# schematic.net
KiCad netlist of a schematic drawn in EAGLE
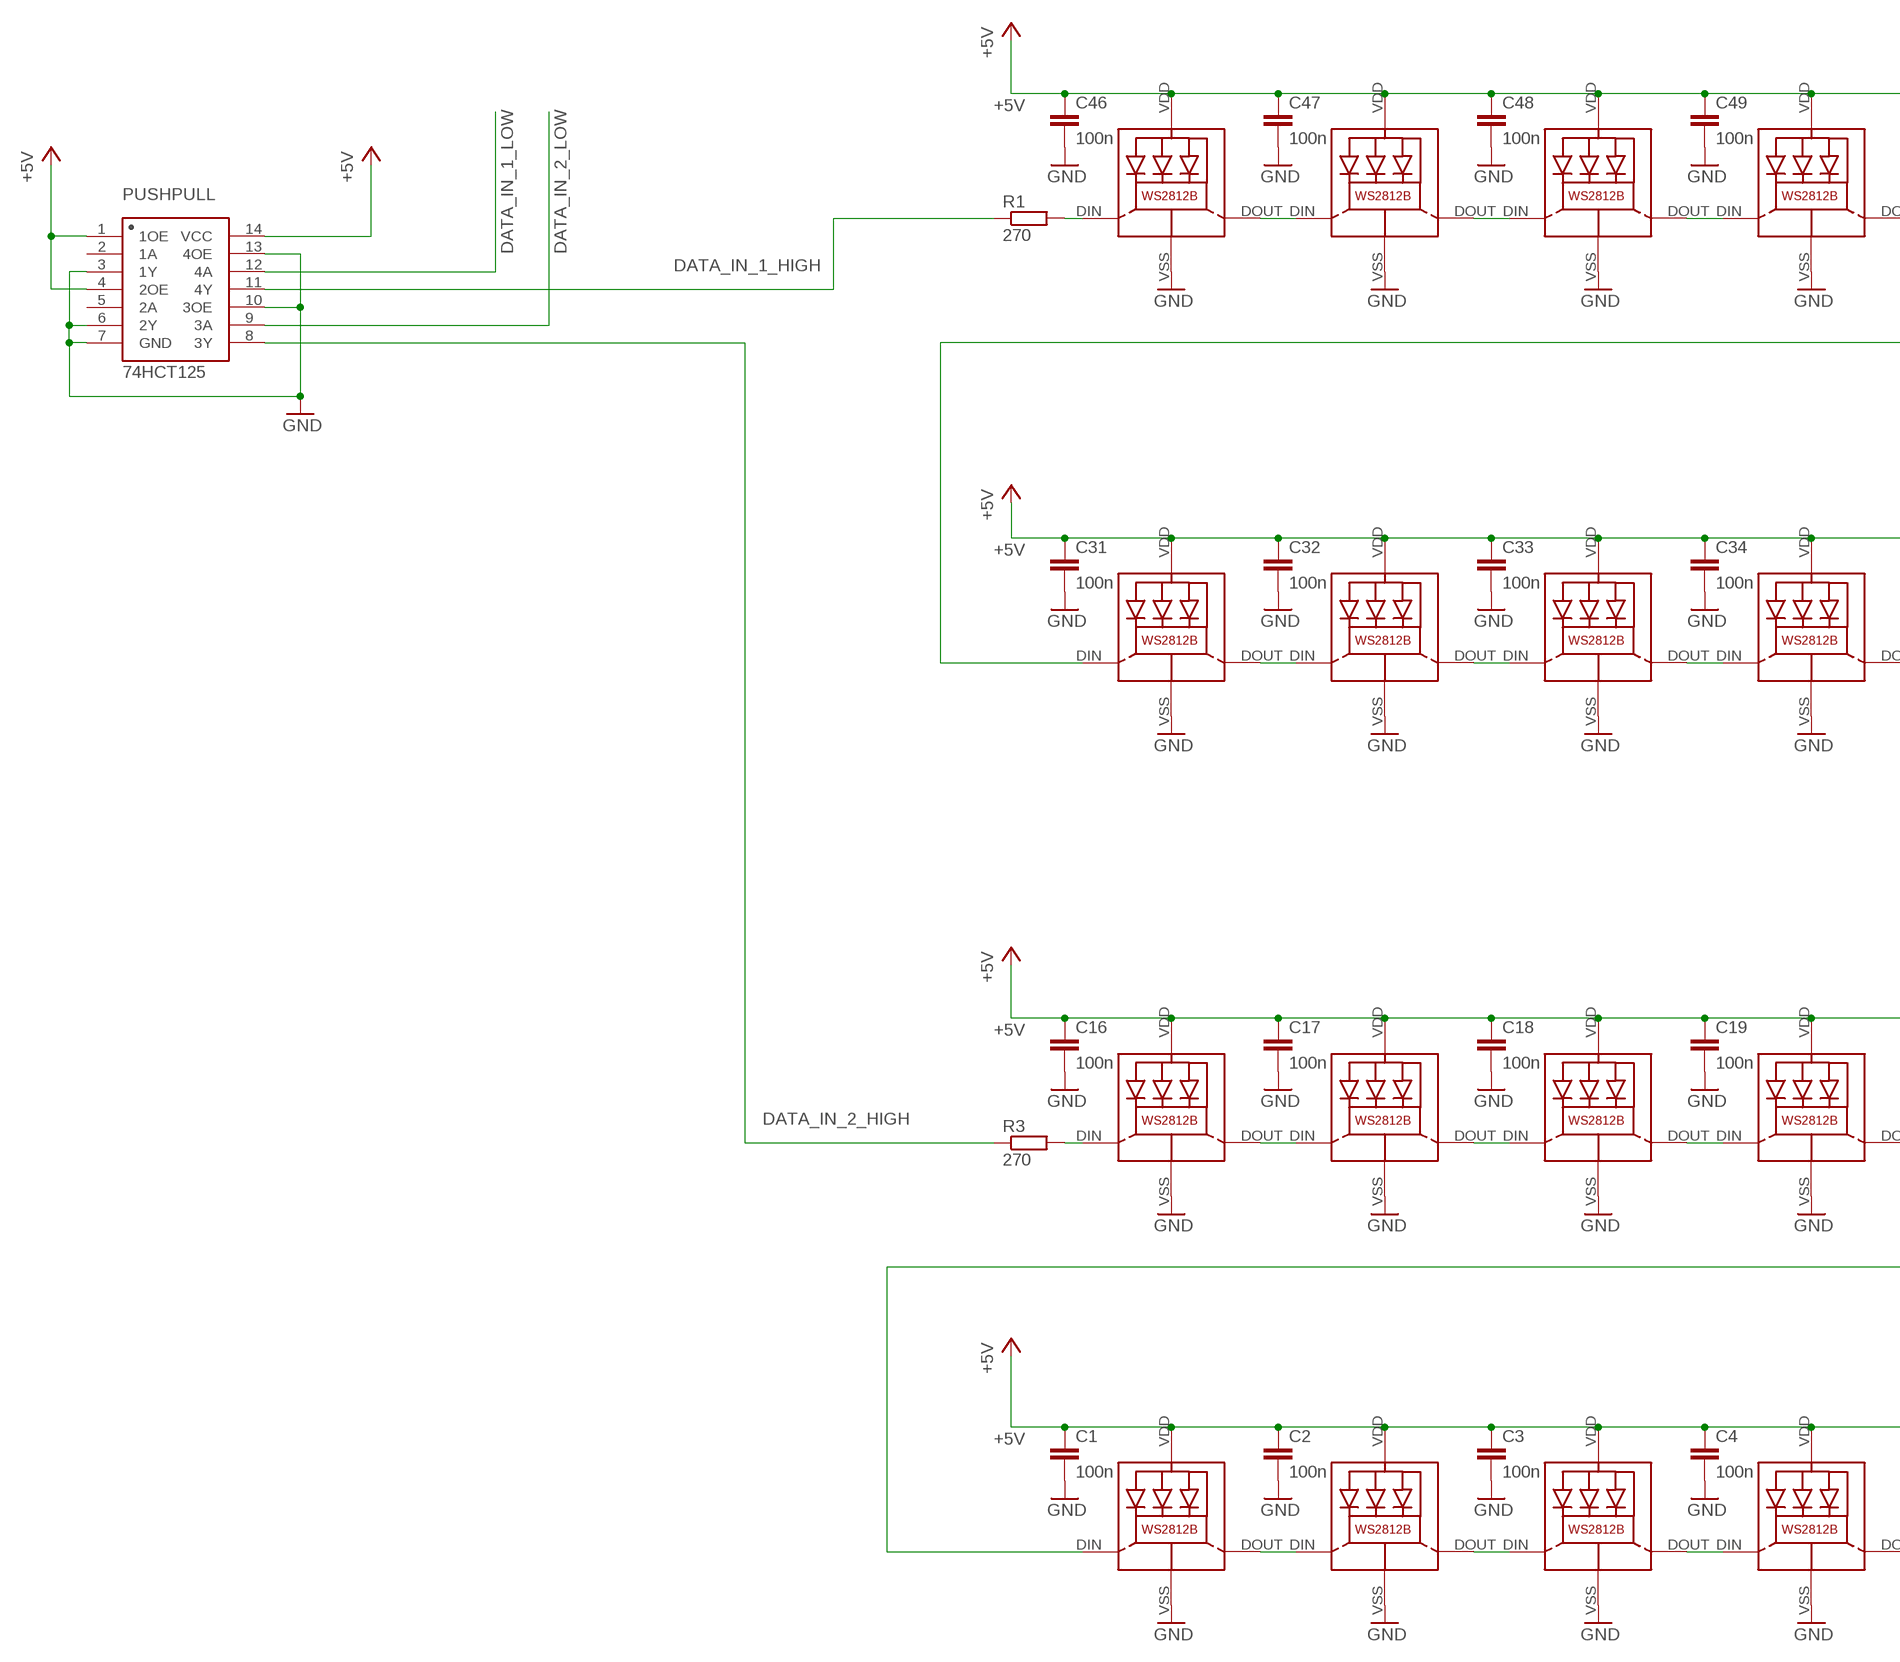
[diagram p0: schematic, sheet 1, part 1 of 2]
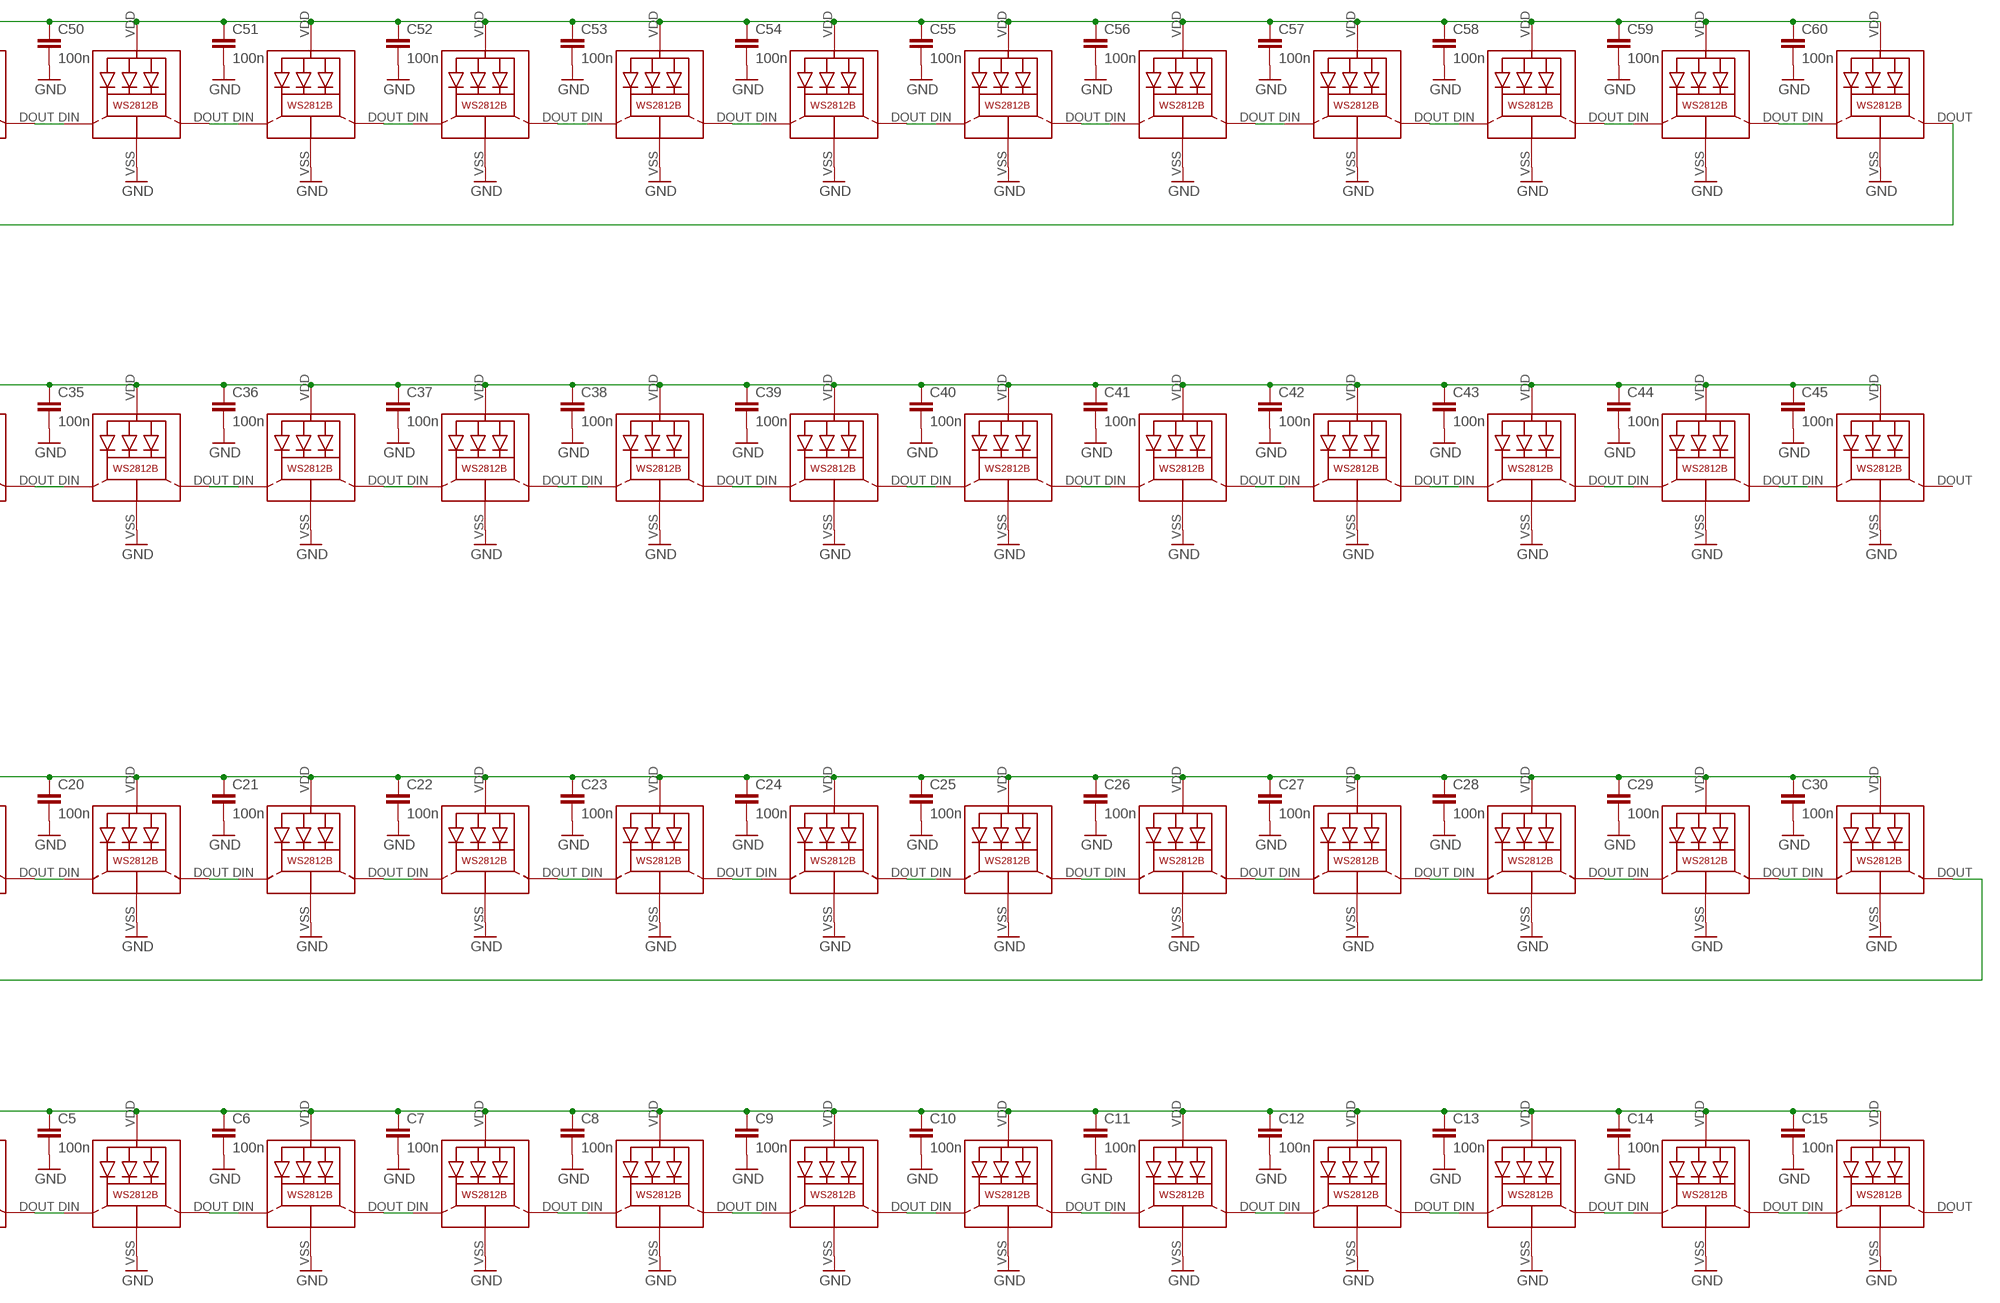
[diagram p1: schematic, sheet 1, part 2 of 2]
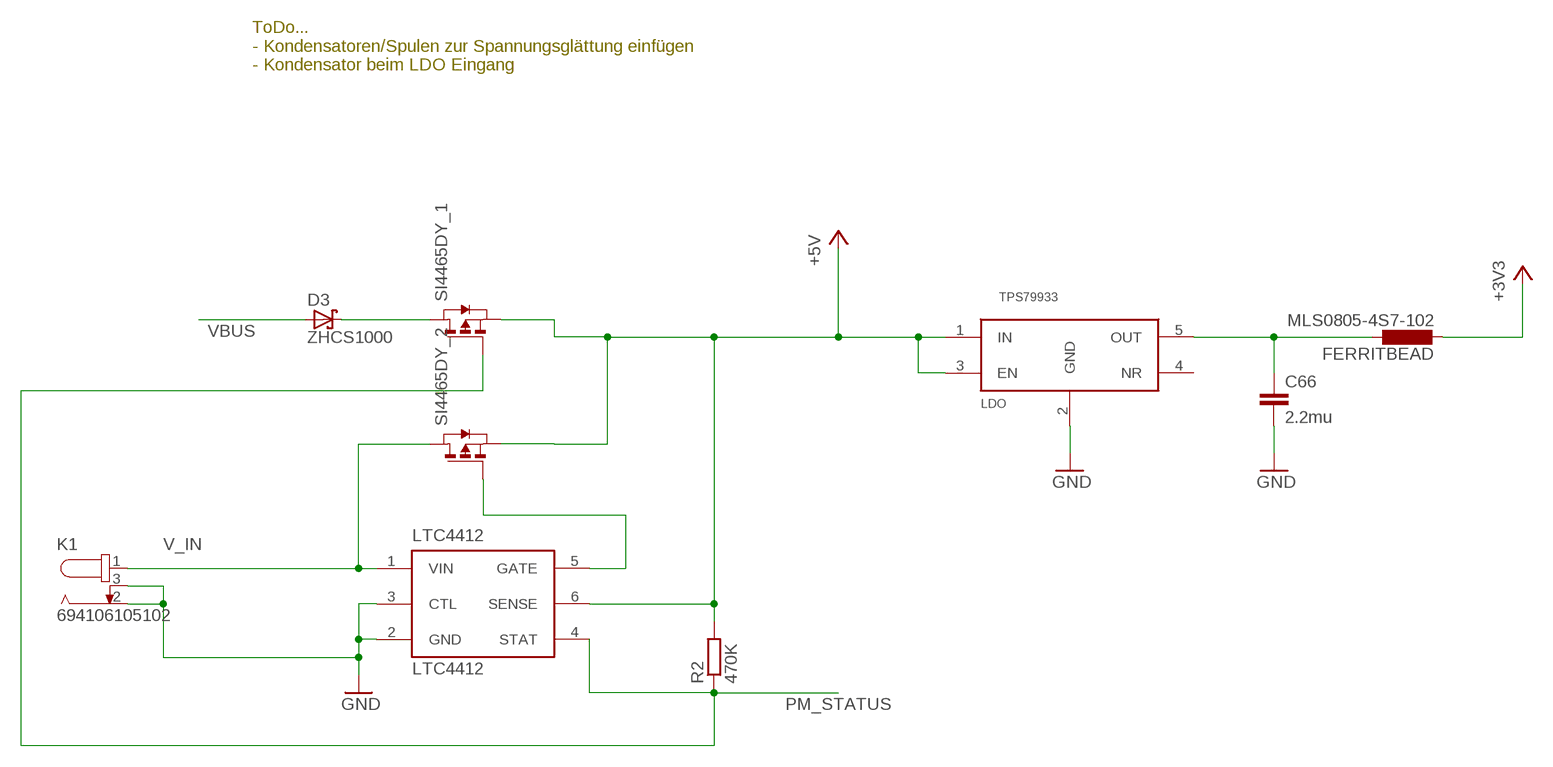
[diagram p2: schematic, sheet 2]
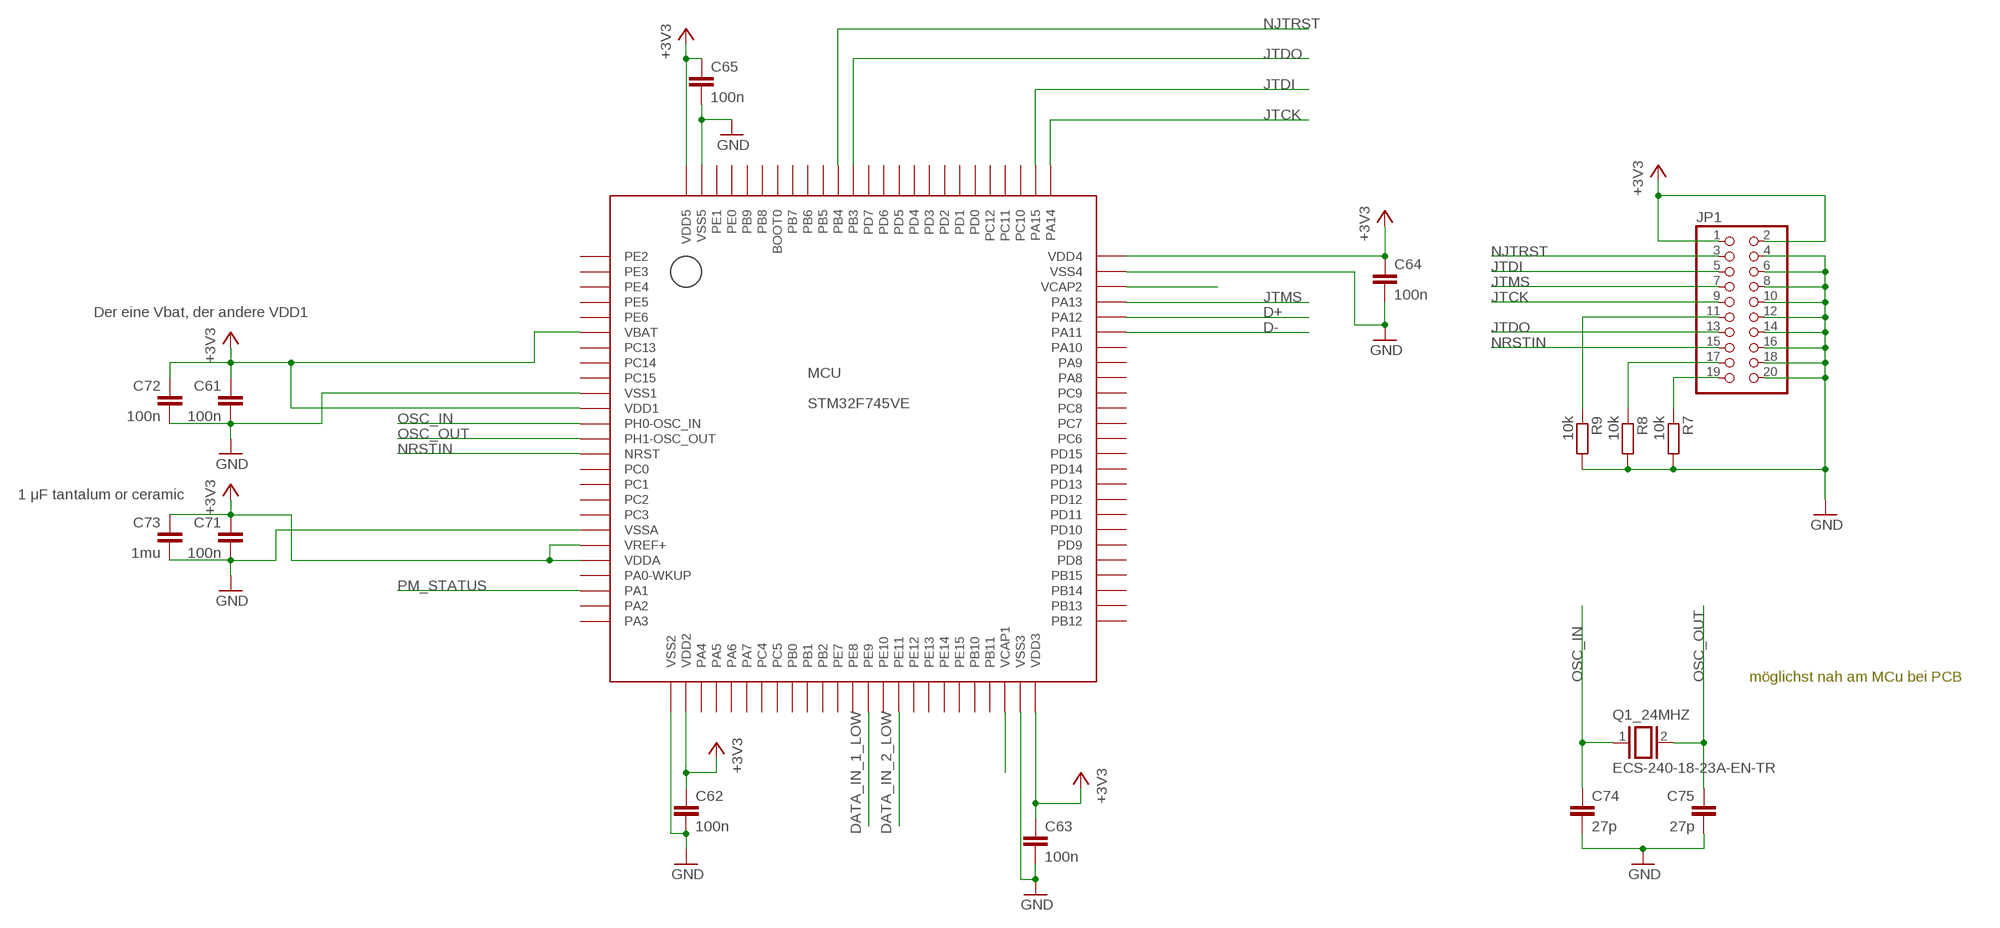
[diagram p3: schematic, sheet 3]
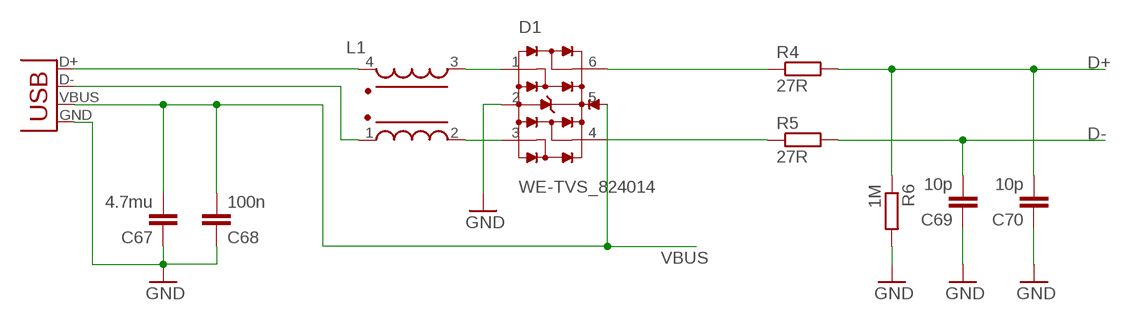
[diagram p4: schematic, sheet 4]
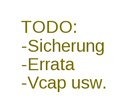
[diagram p5: schematic, sheet 5]

(export (version "E")
  (design (tool "Eeschema 10.0.6"))
  (components
    (comp (ref "C61")
      (value "100n")
      (footprint "eagle-import:C0805")
      (libsource (lib "eagle-import") (part "C-EUC0805"))
    )
    (comp (ref "C62")
      (value "100n")
      (footprint "eagle-import:C0805")
      (libsource (lib "eagle-import") (part "C-EUC0805"))
    )
    (comp (ref "C63")
      (value "100n")
      (footprint "eagle-import:C0805")
      (libsource (lib "eagle-import") (part "C-EUC0805"))
    )
    (comp (ref "C64")
      (value "100n")
      (footprint "eagle-import:C0805")
      (libsource (lib "eagle-import") (part "C-EUC0805"))
    )
    (comp (ref "C65")
      (value "100n")
      (footprint "eagle-import:C0805")
      (libsource (lib "eagle-import") (part "C-EUC0805"))
    )
    (comp (ref "C71")
      (value "100n")
      (footprint "eagle-import:C0805")
      (libsource (lib "eagle-import") (part "C-EUC0805"))
    )
    (comp (ref "C72")
      (value "100n")
      (footprint "eagle-import:C0805")
      (libsource (lib "eagle-import") (part "C-EUC0805"))
    )
    (comp (ref "C73")
      (value "1mu")
      (footprint "eagle-import:C0805")
      (libsource (lib "eagle-import") (part "C-EUC0805"))
    )
    (comp (ref "C74")
      (value "27p")
      (footprint "eagle-import:C0805")
      (libsource (lib "eagle-import") (part "C-EUC0805"))
    )
    (comp (ref "C75")
      (value "27p")
      (footprint "eagle-import:C0805")
      (libsource (lib "eagle-import") (part "C-EUC0805"))
    )
    (comp (ref "JP1")
      (value "PINHD-2X10")
      (footprint "eagle-import:2X10")
      (libsource (lib "eagle-import") (part "PINHD-2X10"))
    )
    (comp (ref "MCU")
      (value "STM32F745VE")
      (footprint "eagle-import:LQFP100")
      (libsource (lib "eagle-import") (part "STM32F745VE"))
    )
    (comp (ref "Q1_24MHZ")
      (value "ECS-240-18-23A-EN-TR")
      (footprint "eagle-import:ESC64A")
      (libsource (lib "eagle-import") (part "ECX64A"))
    )
    (comp (ref "R7")
      (value "10k")
      (footprint "eagle-import:R0805")
      (libsource (lib "eagle-import") (part "R-EU_R0805"))
    )
    (comp (ref "R8")
      (value "10k")
      (footprint "eagle-import:R0805")
      (libsource (lib "eagle-import") (part "R-EU_R0805"))
    )
    (comp (ref "R9")
      (value "10k")
      (footprint "eagle-import:R0805")
      (libsource (lib "eagle-import") (part "R-EU_R0805"))
    )
    (comp (ref "C1")
      (value "100n")
      (footprint "eagle-import:C0805")
      (libsource (lib "eagle-import") (part "C-EUC0805"))
    )
    (comp (ref "C2")
      (value "100n")
      (footprint "eagle-import:C0805")
      (libsource (lib "eagle-import") (part "C-EUC0805"))
    )
    (comp (ref "C3")
      (value "100n")
      (footprint "eagle-import:C0805")
      (libsource (lib "eagle-import") (part "C-EUC0805"))
    )
    (comp (ref "C4")
      (value "100n")
      (footprint "eagle-import:C0805")
      (libsource (lib "eagle-import") (part "C-EUC0805"))
    )
    (comp (ref "C5")
      (value "100n")
      (footprint "eagle-import:C0805")
      (libsource (lib "eagle-import") (part "C-EUC0805"))
    )
    (comp (ref "C6")
      (value "100n")
      (footprint "eagle-import:C0805")
      (libsource (lib "eagle-import") (part "C-EUC0805"))
    )
    (comp (ref "C7")
      (value "100n")
      (footprint "eagle-import:C0805")
      (libsource (lib "eagle-import") (part "C-EUC0805"))
    )
    (comp (ref "C8")
      (value "100n")
      (footprint "eagle-import:C0805")
      (libsource (lib "eagle-import") (part "C-EUC0805"))
    )
    (comp (ref "C9")
      (value "100n")
      (footprint "eagle-import:C0805")
      (libsource (lib "eagle-import") (part "C-EUC0805"))
    )
    (comp (ref "C10")
      (value "100n")
      (footprint "eagle-import:C0805")
      (libsource (lib "eagle-import") (part "C-EUC0805"))
    )
    (comp (ref "C11")
      (value "100n")
      (footprint "eagle-import:C0805")
      (libsource (lib "eagle-import") (part "C-EUC0805"))
    )
    (comp (ref "C12")
      (value "100n")
      (footprint "eagle-import:C0805")
      (libsource (lib "eagle-import") (part "C-EUC0805"))
    )
    (comp (ref "C13")
      (value "100n")
      (footprint "eagle-import:C0805")
      (libsource (lib "eagle-import") (part "C-EUC0805"))
    )
    (comp (ref "C14")
      (value "100n")
      (footprint "eagle-import:C0805")
      (libsource (lib "eagle-import") (part "C-EUC0805"))
    )
    (comp (ref "C15")
      (value "100n")
      (footprint "eagle-import:C0805")
      (libsource (lib "eagle-import") (part "C-EUC0805"))
    )
    (comp (ref "C16")
      (value "100n")
      (footprint "eagle-import:C0805")
      (libsource (lib "eagle-import") (part "C-EUC0805"))
    )
    (comp (ref "C17")
      (value "100n")
      (footprint "eagle-import:C0805")
      (libsource (lib "eagle-import") (part "C-EUC0805"))
    )
    (comp (ref "C18")
      (value "100n")
      (footprint "eagle-import:C0805")
      (libsource (lib "eagle-import") (part "C-EUC0805"))
    )
    (comp (ref "C19")
      (value "100n")
      (footprint "eagle-import:C0805")
      (libsource (lib "eagle-import") (part "C-EUC0805"))
    )
    (comp (ref "C20")
      (value "100n")
      (footprint "eagle-import:C0805")
      (libsource (lib "eagle-import") (part "C-EUC0805"))
    )
    (comp (ref "C21")
      (value "100n")
      (footprint "eagle-import:C0805")
      (libsource (lib "eagle-import") (part "C-EUC0805"))
    )
    (comp (ref "C22")
      (value "100n")
      (footprint "eagle-import:C0805")
      (libsource (lib "eagle-import") (part "C-EUC0805"))
    )
    (comp (ref "C23")
      (value "100n")
      (footprint "eagle-import:C0805")
      (libsource (lib "eagle-import") (part "C-EUC0805"))
    )
    (comp (ref "C24")
      (value "100n")
      (footprint "eagle-import:C0805")
      (libsource (lib "eagle-import") (part "C-EUC0805"))
    )
    (comp (ref "C25")
      (value "100n")
      (footprint "eagle-import:C0805")
      (libsource (lib "eagle-import") (part "C-EUC0805"))
    )
    (comp (ref "C26")
      (value "100n")
      (footprint "eagle-import:C0805")
      (libsource (lib "eagle-import") (part "C-EUC0805"))
    )
    (comp (ref "C27")
      (value "100n")
      (footprint "eagle-import:C0805")
      (libsource (lib "eagle-import") (part "C-EUC0805"))
    )
    (comp (ref "C28")
      (value "100n")
      (footprint "eagle-import:C0805")
      (libsource (lib "eagle-import") (part "C-EUC0805"))
    )
    (comp (ref "C29")
      (value "100n")
      (footprint "eagle-import:C0805")
      (libsource (lib "eagle-import") (part "C-EUC0805"))
    )
    (comp (ref "C30")
      (value "100n")
      (footprint "eagle-import:C0805")
      (libsource (lib "eagle-import") (part "C-EUC0805"))
    )
    (comp (ref "C31")
      (value "100n")
      (footprint "eagle-import:C0805")
      (libsource (lib "eagle-import") (part "C-EUC0805"))
    )
    (comp (ref "C32")
      (value "100n")
      (footprint "eagle-import:C0805")
      (libsource (lib "eagle-import") (part "C-EUC0805"))
    )
    (comp (ref "C33")
      (value "100n")
      (footprint "eagle-import:C0805")
      (libsource (lib "eagle-import") (part "C-EUC0805"))
    )
    (comp (ref "C34")
      (value "100n")
      (footprint "eagle-import:C0805")
      (libsource (lib "eagle-import") (part "C-EUC0805"))
    )
    (comp (ref "C35")
      (value "100n")
      (footprint "eagle-import:C0805")
      (libsource (lib "eagle-import") (part "C-EUC0805"))
    )
    (comp (ref "C36")
      (value "100n")
      (footprint "eagle-import:C0805")
      (libsource (lib "eagle-import") (part "C-EUC0805"))
    )
    (comp (ref "C37")
      (value "100n")
      (footprint "eagle-import:C0805")
      (libsource (lib "eagle-import") (part "C-EUC0805"))
    )
    (comp (ref "C38")
      (value "100n")
      (footprint "eagle-import:C0805")
      (libsource (lib "eagle-import") (part "C-EUC0805"))
    )
    (comp (ref "C39")
      (value "100n")
      (footprint "eagle-import:C0805")
      (libsource (lib "eagle-import") (part "C-EUC0805"))
    )
    (comp (ref "C40")
      (value "100n")
      (footprint "eagle-import:C0805")
      (libsource (lib "eagle-import") (part "C-EUC0805"))
    )
    (comp (ref "C41")
      (value "100n")
      (footprint "eagle-import:C0805")
      (libsource (lib "eagle-import") (part "C-EUC0805"))
    )
    (comp (ref "C42")
      (value "100n")
      (footprint "eagle-import:C0805")
      (libsource (lib "eagle-import") (part "C-EUC0805"))
    )
    (comp (ref "C43")
      (value "100n")
      (footprint "eagle-import:C0805")
      (libsource (lib "eagle-import") (part "C-EUC0805"))
    )
    (comp (ref "C44")
      (value "100n")
      (footprint "eagle-import:C0805")
      (libsource (lib "eagle-import") (part "C-EUC0805"))
    )
    (comp (ref "C45")
      (value "100n")
      (footprint "eagle-import:C0805")
      (libsource (lib "eagle-import") (part "C-EUC0805"))
    )
    (comp (ref "C46")
      (value "100n")
      (footprint "eagle-import:C0805")
      (libsource (lib "eagle-import") (part "C-EUC0805"))
    )
    (comp (ref "C47")
      (value "100n")
      (footprint "eagle-import:C0805")
      (libsource (lib "eagle-import") (part "C-EUC0805"))
    )
    (comp (ref "C48")
      (value "100n")
      (footprint "eagle-import:C0805")
      (libsource (lib "eagle-import") (part "C-EUC0805"))
    )
    (comp (ref "C49")
      (value "100n")
      (footprint "eagle-import:C0805")
      (libsource (lib "eagle-import") (part "C-EUC0805"))
    )
    (comp (ref "C50")
      (value "100n")
      (footprint "eagle-import:C0805")
      (libsource (lib "eagle-import") (part "C-EUC0805"))
    )
    (comp (ref "C51")
      (value "100n")
      (footprint "eagle-import:C0805")
      (libsource (lib "eagle-import") (part "C-EUC0805"))
    )
    (comp (ref "C52")
      (value "100n")
      (footprint "eagle-import:C0805")
      (libsource (lib "eagle-import") (part "C-EUC0805"))
    )
    (comp (ref "C53")
      (value "100n")
      (footprint "eagle-import:C0805")
      (libsource (lib "eagle-import") (part "C-EUC0805"))
    )
    (comp (ref "C54")
      (value "100n")
      (footprint "eagle-import:C0805")
      (libsource (lib "eagle-import") (part "C-EUC0805"))
    )
    (comp (ref "C55")
      (value "100n")
      (footprint "eagle-import:C0805")
      (libsource (lib "eagle-import") (part "C-EUC0805"))
    )
    (comp (ref "C56")
      (value "100n")
      (footprint "eagle-import:C0805")
      (libsource (lib "eagle-import") (part "C-EUC0805"))
    )
    (comp (ref "C57")
      (value "100n")
      (footprint "eagle-import:C0805")
      (libsource (lib "eagle-import") (part "C-EUC0805"))
    )
    (comp (ref "C58")
      (value "100n")
      (footprint "eagle-import:C0805")
      (libsource (lib "eagle-import") (part "C-EUC0805"))
    )
    (comp (ref "C59")
      (value "100n")
      (footprint "eagle-import:C0805")
      (libsource (lib "eagle-import") (part "C-EUC0805"))
    )
    (comp (ref "C60")
      (value "100n")
      (footprint "eagle-import:C0805")
      (libsource (lib "eagle-import") (part "C-EUC0805"))
    )
    (comp (ref "LED1")
      (value "WS2812B")
      (footprint "eagle-import:WS2812B")
      (libsource (lib "eagle-import") (part "WS2812B"))
    )
    (comp (ref "LED2")
      (value "WS2812B")
      (footprint "eagle-import:WS2812B")
      (libsource (lib "eagle-import") (part "WS2812B"))
    )
    (comp (ref "LED3")
      (value "WS2812B")
      (footprint "eagle-import:WS2812B")
      (libsource (lib "eagle-import") (part "WS2812B"))
    )
    (comp (ref "LED4")
      (value "WS2812B")
      (footprint "eagle-import:WS2812B")
      (libsource (lib "eagle-import") (part "WS2812B"))
    )
    (comp (ref "LED5")
      (value "WS2812B")
      (footprint "eagle-import:WS2812B")
      (libsource (lib "eagle-import") (part "WS2812B"))
    )
    (comp (ref "LED6")
      (value "WS2812B")
      (footprint "eagle-import:WS2812B")
      (libsource (lib "eagle-import") (part "WS2812B"))
    )
    (comp (ref "LED7")
      (value "WS2812B")
      (footprint "eagle-import:WS2812B")
      (libsource (lib "eagle-import") (part "WS2812B"))
    )
    (comp (ref "LED8")
      (value "WS2812B")
      (footprint "eagle-import:WS2812B")
      (libsource (lib "eagle-import") (part "WS2812B"))
    )
    (comp (ref "LED9")
      (value "WS2812B")
      (footprint "eagle-import:WS2812B")
      (libsource (lib "eagle-import") (part "WS2812B"))
    )
    (comp (ref "LED10")
      (value "WS2812B")
      (footprint "eagle-import:WS2812B")
      (libsource (lib "eagle-import") (part "WS2812B"))
    )
    (comp (ref "LED11")
      (value "WS2812B")
      (footprint "eagle-import:WS2812B")
      (libsource (lib "eagle-import") (part "WS2812B"))
    )
    (comp (ref "LED12")
      (value "WS2812B")
      (footprint "eagle-import:WS2812B")
      (libsource (lib "eagle-import") (part "WS2812B"))
    )
    (comp (ref "LED13")
      (value "WS2812B")
      (footprint "eagle-import:WS2812B")
      (libsource (lib "eagle-import") (part "WS2812B"))
    )
    (comp (ref "LED14")
      (value "WS2812B")
      (footprint "eagle-import:WS2812B")
      (libsource (lib "eagle-import") (part "WS2812B"))
    )
    (comp (ref "LED15")
      (value "WS2812B")
      (footprint "eagle-import:WS2812B")
      (libsource (lib "eagle-import") (part "WS2812B"))
    )
    (comp (ref "LED16")
      (value "WS2812B")
      (footprint "eagle-import:WS2812B")
      (libsource (lib "eagle-import") (part "WS2812B"))
    )
    (comp (ref "LED17")
      (value "WS2812B")
      (footprint "eagle-import:WS2812B")
      (libsource (lib "eagle-import") (part "WS2812B"))
    )
    (comp (ref "LED18")
      (value "WS2812B")
      (footprint "eagle-import:WS2812B")
      (libsource (lib "eagle-import") (part "WS2812B"))
    )
    (comp (ref "LED19")
      (value "WS2812B")
      (footprint "eagle-import:WS2812B")
      (libsource (lib "eagle-import") (part "WS2812B"))
    )
    (comp (ref "LED20")
      (value "WS2812B")
      (footprint "eagle-import:WS2812B")
      (libsource (lib "eagle-import") (part "WS2812B"))
    )
    (comp (ref "LED21")
      (value "WS2812B")
      (footprint "eagle-import:WS2812B")
      (libsource (lib "eagle-import") (part "WS2812B"))
    )
    (comp (ref "LED22")
      (value "WS2812B")
      (footprint "eagle-import:WS2812B")
      (libsource (lib "eagle-import") (part "WS2812B"))
    )
    (comp (ref "LED23")
      (value "WS2812B")
      (footprint "eagle-import:WS2812B")
      (libsource (lib "eagle-import") (part "WS2812B"))
    )
    (comp (ref "LED24")
      (value "WS2812B")
      (footprint "eagle-import:WS2812B")
      (libsource (lib "eagle-import") (part "WS2812B"))
    )
    (comp (ref "LED25")
      (value "WS2812B")
      (footprint "eagle-import:WS2812B")
      (libsource (lib "eagle-import") (part "WS2812B"))
    )
    (comp (ref "LED26")
      (value "WS2812B")
      (footprint "eagle-import:WS2812B")
      (libsource (lib "eagle-import") (part "WS2812B"))
    )
    (comp (ref "LED27")
      (value "WS2812B")
      (footprint "eagle-import:WS2812B")
      (libsource (lib "eagle-import") (part "WS2812B"))
    )
    (comp (ref "LED28")
      (value "WS2812B")
      (footprint "eagle-import:WS2812B")
      (libsource (lib "eagle-import") (part "WS2812B"))
    )
    (comp (ref "LED29")
      (value "WS2812B")
      (footprint "eagle-import:WS2812B")
      (libsource (lib "eagle-import") (part "WS2812B"))
    )
    (comp (ref "LED30")
      (value "WS2812B")
      (footprint "eagle-import:WS2812B")
      (libsource (lib "eagle-import") (part "WS2812B"))
    )
    (comp (ref "LED31")
      (value "WS2812B")
      (footprint "eagle-import:WS2812B")
      (libsource (lib "eagle-import") (part "WS2812B"))
    )
    (comp (ref "LED32")
      (value "WS2812B")
      (footprint "eagle-import:WS2812B")
      (libsource (lib "eagle-import") (part "WS2812B"))
    )
    (comp (ref "LED33")
      (value "WS2812B")
      (footprint "eagle-import:WS2812B")
      (libsource (lib "eagle-import") (part "WS2812B"))
    )
    (comp (ref "LED34")
      (value "WS2812B")
      (footprint "eagle-import:WS2812B")
      (libsource (lib "eagle-import") (part "WS2812B"))
    )
    (comp (ref "LED35")
      (value "WS2812B")
      (footprint "eagle-import:WS2812B")
      (libsource (lib "eagle-import") (part "WS2812B"))
    )
    (comp (ref "LED36")
      (value "WS2812B")
      (footprint "eagle-import:WS2812B")
      (libsource (lib "eagle-import") (part "WS2812B"))
    )
    (comp (ref "LED37")
      (value "WS2812B")
      (footprint "eagle-import:WS2812B")
      (libsource (lib "eagle-import") (part "WS2812B"))
    )
    (comp (ref "LED38")
      (value "WS2812B")
      (footprint "eagle-import:WS2812B")
      (libsource (lib "eagle-import") (part "WS2812B"))
    )
    (comp (ref "LED39")
      (value "WS2812B")
      (footprint "eagle-import:WS2812B")
      (libsource (lib "eagle-import") (part "WS2812B"))
    )
    (comp (ref "LED40")
      (value "WS2812B")
      (footprint "eagle-import:WS2812B")
      (libsource (lib "eagle-import") (part "WS2812B"))
    )
    (comp (ref "LED41")
      (value "WS2812B")
      (footprint "eagle-import:WS2812B")
      (libsource (lib "eagle-import") (part "WS2812B"))
    )
    (comp (ref "LED42")
      (value "WS2812B")
      (footprint "eagle-import:WS2812B")
      (libsource (lib "eagle-import") (part "WS2812B"))
    )
    (comp (ref "LED43")
      (value "WS2812B")
      (footprint "eagle-import:WS2812B")
      (libsource (lib "eagle-import") (part "WS2812B"))
    )
    (comp (ref "LED44")
      (value "WS2812B")
      (footprint "eagle-import:WS2812B")
      (libsource (lib "eagle-import") (part "WS2812B"))
    )
    (comp (ref "LED45")
      (value "WS2812B")
      (footprint "eagle-import:WS2812B")
      (libsource (lib "eagle-import") (part "WS2812B"))
    )
    (comp (ref "LED46")
      (value "WS2812B")
      (footprint "eagle-import:WS2812B")
      (libsource (lib "eagle-import") (part "WS2812B"))
    )
    (comp (ref "LED47")
      (value "WS2812B")
      (footprint "eagle-import:WS2812B")
      (libsource (lib "eagle-import") (part "WS2812B"))
    )
    (comp (ref "LED48")
      (value "WS2812B")
      (footprint "eagle-import:WS2812B")
      (libsource (lib "eagle-import") (part "WS2812B"))
    )
    (comp (ref "LED49")
      (value "WS2812B")
      (footprint "eagle-import:WS2812B")
      (libsource (lib "eagle-import") (part "WS2812B"))
    )
    (comp (ref "LED50")
      (value "WS2812B")
      (footprint "eagle-import:WS2812B")
      (libsource (lib "eagle-import") (part "WS2812B"))
    )
    (comp (ref "LED51")
      (value "WS2812B")
      (footprint "eagle-import:WS2812B")
      (libsource (lib "eagle-import") (part "WS2812B"))
    )
    (comp (ref "LED52")
      (value "WS2812B")
      (footprint "eagle-import:WS2812B")
      (libsource (lib "eagle-import") (part "WS2812B"))
    )
    (comp (ref "LED53")
      (value "WS2812B")
      (footprint "eagle-import:WS2812B")
      (libsource (lib "eagle-import") (part "WS2812B"))
    )
    (comp (ref "LED54")
      (value "WS2812B")
      (footprint "eagle-import:WS2812B")
      (libsource (lib "eagle-import") (part "WS2812B"))
    )
    (comp (ref "LED55")
      (value "WS2812B")
      (footprint "eagle-import:WS2812B")
      (libsource (lib "eagle-import") (part "WS2812B"))
    )
    (comp (ref "LED56")
      (value "WS2812B")
      (footprint "eagle-import:WS2812B")
      (libsource (lib "eagle-import") (part "WS2812B"))
    )
    (comp (ref "LED57")
      (value "WS2812B")
      (footprint "eagle-import:WS2812B")
      (libsource (lib "eagle-import") (part "WS2812B"))
    )
    (comp (ref "LED58")
      (value "WS2812B")
      (footprint "eagle-import:WS2812B")
      (libsource (lib "eagle-import") (part "WS2812B"))
    )
    (comp (ref "LED59")
      (value "WS2812B")
      (footprint "eagle-import:WS2812B")
      (libsource (lib "eagle-import") (part "WS2812B"))
    )
    (comp (ref "LED60")
      (value "WS2812B")
      (footprint "eagle-import:WS2812B")
      (libsource (lib "eagle-import") (part "WS2812B"))
    )
    (comp (ref "PUSHPULL")
      (value "74HCT125")
      (footprint "eagle-import:SO-14DW")
      (libsource (lib "eagle-import") (part "74HCT125"))
    )
    (comp (ref "R1")
      (value "270")
      (footprint "eagle-import:R0805")
      (libsource (lib "eagle-import") (part "R-EU_R0805"))
    )
    (comp (ref "R3")
      (value "270")
      (footprint "eagle-import:R0805")
      (libsource (lib "eagle-import") (part "R-EU_R0805"))
    )
    (comp (ref "C67")
      (value "4.7mu")
      (footprint "eagle-import:C0805")
      (libsource (lib "eagle-import") (part "C-EUC0805"))
    )
    (comp (ref "C68")
      (value "100n")
      (footprint "eagle-import:C0805")
      (libsource (lib "eagle-import") (part "C-EUC0805"))
    )
    (comp (ref "C69")
      (value "10p")
      (footprint "eagle-import:C0805")
      (libsource (lib "eagle-import") (part "C-EUC0805"))
    )
    (comp (ref "C70")
      (value "10p")
      (footprint "eagle-import:C0805")
      (libsource (lib "eagle-import") (part "C-EUC0805"))
    )
    (comp (ref "D1")
      (value "WE-TVS_824014")
      (footprint "eagle-import:WE-TVS_SOT23-6L")
      (libsource (lib "eagle-import") (part "WE-TVS_824014"))
    )
    (comp (ref "L1")
      (value "WE-CNSW_0805")
      (footprint "eagle-import:WE-CNSW_0805")
      (libsource (lib "eagle-import") (part "WE-CNSW_0805"))
    )
    (comp (ref "R4")
      (value "27R")
      (footprint "eagle-import:R0805")
      (libsource (lib "eagle-import") (part "R-EU_R0805"))
    )
    (comp (ref "R5")
      (value "27R")
      (footprint "eagle-import:R0805")
      (libsource (lib "eagle-import") (part "R-EU_R0805"))
    )
    (comp (ref "R6")
      (value "1M")
      (footprint "eagle-import:R0805")
      (libsource (lib "eagle-import") (part "R-EU_R0805"))
    )
    (comp (ref "X1")
      (value "USBSMD")
      (footprint "eagle-import:USB-MINIB")
      (libsource (lib "eagle-import") (part "USBSMD"))
    )
    (comp (ref "C66")
      (value "2.2mu")
      (footprint "eagle-import:C0805")
      (libsource (lib "eagle-import") (part "C-EUC0805"))
    )
    (comp (ref "D3")
      (value "ZHCS1000")
      (footprint "eagle-import:SOT23")
      (libsource (lib "eagle-import") (part "ZHCS1000"))
    )
    (comp (ref "FERRITBEAD")
      (value "MLS0805-4S7-102")
      (footprint "eagle-import:M0805")
      (libsource (lib "eagle-import") (part "MLS0805-4S7-102"))
    )
    (comp (ref "K1")
      (value "694106105102")
      (footprint "eagle-import:694106105102")
      (libsource (lib "eagle-import") (part "694106105102"))
    )
    (comp (ref "LDO")
      (value "TPS79933")
      (footprint "eagle-import:SOT23-DBV")
      (libsource (lib "eagle-import") (part "TPS79933"))
    )
    (comp (ref "LTC4412")
      (value "LTC4412")
      (footprint "eagle-import:SOT23-6L")
      (libsource (lib "eagle-import") (part "LTC4412"))
    )
    (comp (ref "R2")
      (value "470K")
      (footprint "eagle-import:R0805")
      (libsource (lib "eagle-import") (part "R-EU_R0805"))
    )
    (comp (ref "SI4465DY_1")
      (value "PMOSSOT223SO8")
      (footprint "eagle-import:SO08")
      (libsource (lib "eagle-import") (part "PMOSSOT223SO8"))
    )
    (comp (ref "SI4465DY_2")
      (value "PMOSSOT223SO8")
      (footprint "eagle-import:SO08")
      (libsource (lib "eagle-import") (part "PMOSSOT223SO8"))
    )
  )
  (nets
    (net (code "1") (name "+3V3") (class "Default")
      (node (ref "C61") (pin "1") (pinfunction "1_1") (pintype "passive"))
      (node (ref "C62") (pin "1") (pinfunction "1_1") (pintype "passive"))
      (node (ref "C63") (pin "1") (pinfunction "1_1") (pintype "passive"))
      (node (ref "C64") (pin "1") (pinfunction "1_1") (pintype "passive"))
      (node (ref "C65") (pin "1") (pinfunction "1_1") (pintype "passive"))
      (node (ref "C71") (pin "1") (pinfunction "1_1") (pintype "passive"))
      (node (ref "C72") (pin "1") (pinfunction "1_1") (pintype "passive"))
      (node (ref "C73") (pin "1") (pinfunction "1_1") (pintype "passive"))
      (node (ref "FERRITBEAD") (pin "2") (pinfunction "2_2") (pintype "passive"))
      (node (ref "JP1") (pin "1") (pinfunction "1_1") (pintype "passive"))
      (node (ref "JP1") (pin "2") (pinfunction "2_2") (pintype "passive"))
      (node (ref "MCU") (pin "100") (pinfunction "VDD5_100") (pintype "power_in"))
      (node (ref "MCU") (pin "11") (pinfunction "VDD1_11") (pintype "power_in"))
      (node (ref "MCU") (pin "20") (pinfunction "VREF+_20") (pintype "power_in"))
      (node (ref "MCU") (pin "21") (pinfunction "VDDA_21") (pintype "power_in"))
      (node (ref "MCU") (pin "27") (pinfunction "VDD2_27") (pintype "power_in"))
      (node (ref "MCU") (pin "50") (pinfunction "VDD3_50") (pintype "power_in"))
      (node (ref "MCU") (pin "6") (pinfunction "VBAT_6") (pintype "power_in"))
      (node (ref "MCU") (pin "75") (pinfunction "VDD4_75") (pintype "power_in"))
    )
    (net (code "2") (name "+5V") (class "Default")
      (node (ref "C1") (pin "1") (pinfunction "1_1") (pintype "passive"))
      (node (ref "C10") (pin "1") (pinfunction "1_1") (pintype "passive"))
      (node (ref "C11") (pin "1") (pinfunction "1_1") (pintype "passive"))
      (node (ref "C12") (pin "1") (pinfunction "1_1") (pintype "passive"))
      (node (ref "C13") (pin "1") (pinfunction "1_1") (pintype "passive"))
      (node (ref "C14") (pin "1") (pinfunction "1_1") (pintype "passive"))
      (node (ref "C15") (pin "1") (pinfunction "1_1") (pintype "passive"))
      (node (ref "C16") (pin "1") (pinfunction "1_1") (pintype "passive"))
      (node (ref "C17") (pin "1") (pinfunction "1_1") (pintype "passive"))
      (node (ref "C18") (pin "1") (pinfunction "1_1") (pintype "passive"))
      (node (ref "C19") (pin "1") (pinfunction "1_1") (pintype "passive"))
      (node (ref "C2") (pin "1") (pinfunction "1_1") (pintype "passive"))
      (node (ref "C20") (pin "1") (pinfunction "1_1") (pintype "passive"))
      (node (ref "C21") (pin "1") (pinfunction "1_1") (pintype "passive"))
      (node (ref "C22") (pin "1") (pinfunction "1_1") (pintype "passive"))
      (node (ref "C23") (pin "1") (pinfunction "1_1") (pintype "passive"))
      (node (ref "C24") (pin "1") (pinfunction "1_1") (pintype "passive"))
      (node (ref "C25") (pin "1") (pinfunction "1_1") (pintype "passive"))
      (node (ref "C26") (pin "1") (pinfunction "1_1") (pintype "passive"))
      (node (ref "C27") (pin "1") (pinfunction "1_1") (pintype "passive"))
      (node (ref "C28") (pin "1") (pinfunction "1_1") (pintype "passive"))
      (node (ref "C29") (pin "1") (pinfunction "1_1") (pintype "passive"))
      (node (ref "C3") (pin "1") (pinfunction "1_1") (pintype "passive"))
      (node (ref "C30") (pin "1") (pinfunction "1_1") (pintype "passive"))
      (node (ref "C31") (pin "1") (pinfunction "1_1") (pintype "passive"))
      (node (ref "C32") (pin "1") (pinfunction "1_1") (pintype "passive"))
      (node (ref "C33") (pin "1") (pinfunction "1_1") (pintype "passive"))
      (node (ref "C34") (pin "1") (pinfunction "1_1") (pintype "passive"))
      (node (ref "C35") (pin "1") (pinfunction "1_1") (pintype "passive"))
      (node (ref "C36") (pin "1") (pinfunction "1_1") (pintype "passive"))
      (node (ref "C37") (pin "1") (pinfunction "1_1") (pintype "passive"))
      (node (ref "C38") (pin "1") (pinfunction "1_1") (pintype "passive"))
      (node (ref "C39") (pin "1") (pinfunction "1_1") (pintype "passive"))
      (node (ref "C4") (pin "1") (pinfunction "1_1") (pintype "passive"))
      (node (ref "C40") (pin "1") (pinfunction "1_1") (pintype "passive"))
      (node (ref "C41") (pin "1") (pinfunction "1_1") (pintype "passive"))
      (node (ref "C42") (pin "1") (pinfunction "1_1") (pintype "passive"))
      (node (ref "C43") (pin "1") (pinfunction "1_1") (pintype "passive"))
      (node (ref "C44") (pin "1") (pinfunction "1_1") (pintype "passive"))
      (node (ref "C45") (pin "1") (pinfunction "1_1") (pintype "passive"))
      (node (ref "C46") (pin "1") (pinfunction "1_1") (pintype "passive"))
      (node (ref "C47") (pin "1") (pinfunction "1_1") (pintype "passive"))
      (node (ref "C48") (pin "1") (pinfunction "1_1") (pintype "passive"))
      (node (ref "C49") (pin "1") (pinfunction "1_1") (pintype "passive"))
      (node (ref "C5") (pin "1") (pinfunction "1_1") (pintype "passive"))
      (node (ref "C50") (pin "1") (pinfunction "1_1") (pintype "passive"))
      (node (ref "C51") (pin "1") (pinfunction "1_1") (pintype "passive"))
      (node (ref "C52") (pin "1") (pinfunction "1_1") (pintype "passive"))
      (node (ref "C53") (pin "1") (pinfunction "1_1") (pintype "passive"))
      (node (ref "C54") (pin "1") (pinfunction "1_1") (pintype "passive"))
      (node (ref "C55") (pin "1") (pinfunction "1_1") (pintype "passive"))
      (node (ref "C56") (pin "1") (pinfunction "1_1") (pintype "passive"))
      (node (ref "C57") (pin "1") (pinfunction "1_1") (pintype "passive"))
      (node (ref "C58") (pin "1") (pinfunction "1_1") (pintype "passive"))
      (node (ref "C59") (pin "1") (pinfunction "1_1") (pintype "passive"))
      (node (ref "C6") (pin "1") (pinfunction "1_1") (pintype "passive"))
      (node (ref "C60") (pin "1") (pinfunction "1_1") (pintype "passive"))
      (node (ref "C7") (pin "1") (pinfunction "1_1") (pintype "passive"))
      (node (ref "C8") (pin "1") (pinfunction "1_1") (pintype "passive"))
      (node (ref "C9") (pin "1") (pinfunction "1_1") (pintype "passive"))
      (node (ref "LDO") (pin "1") (pinfunction "IN_1") (pintype "bidirectional"))
      (node (ref "LDO") (pin "3") (pinfunction "EN_3") (pintype "bidirectional"))
      (node (ref "LED1") (pin "VDD") (pinfunction "VDD_VDD") (pintype "power_in"))
      (node (ref "LED10") (pin "VDD") (pinfunction "VDD_VDD") (pintype "power_in"))
      (node (ref "LED11") (pin "VDD") (pinfunction "VDD_VDD") (pintype "power_in"))
      (node (ref "LED12") (pin "VDD") (pinfunction "VDD_VDD") (pintype "power_in"))
      (node (ref "LED13") (pin "VDD") (pinfunction "VDD_VDD") (pintype "power_in"))
      (node (ref "LED14") (pin "VDD") (pinfunction "VDD_VDD") (pintype "power_in"))
      (node (ref "LED15") (pin "VDD") (pinfunction "VDD_VDD") (pintype "power_in"))
      (node (ref "LED16") (pin "VDD") (pinfunction "VDD_VDD") (pintype "power_in"))
      (node (ref "LED17") (pin "VDD") (pinfunction "VDD_VDD") (pintype "power_in"))
      (node (ref "LED18") (pin "VDD") (pinfunction "VDD_VDD") (pintype "power_in"))
      (node (ref "LED19") (pin "VDD") (pinfunction "VDD_VDD") (pintype "power_in"))
      (node (ref "LED2") (pin "VDD") (pinfunction "VDD_VDD") (pintype "power_in"))
      (node (ref "LED20") (pin "VDD") (pinfunction "VDD_VDD") (pintype "power_in"))
      (node (ref "LED21") (pin "VDD") (pinfunction "VDD_VDD") (pintype "power_in"))
      (node (ref "LED22") (pin "VDD") (pinfunction "VDD_VDD") (pintype "power_in"))
      (node (ref "LED23") (pin "VDD") (pinfunction "VDD_VDD") (pintype "power_in"))
      (node (ref "LED24") (pin "VDD") (pinfunction "VDD_VDD") (pintype "power_in"))
      (node (ref "LED25") (pin "VDD") (pinfunction "VDD_VDD") (pintype "power_in"))
      (node (ref "LED26") (pin "VDD") (pinfunction "VDD_VDD") (pintype "power_in"))
      (node (ref "LED27") (pin "VDD") (pinfunction "VDD_VDD") (pintype "power_in"))
      (node (ref "LED28") (pin "VDD") (pinfunction "VDD_VDD") (pintype "power_in"))
      (node (ref "LED29") (pin "VDD") (pinfunction "VDD_VDD") (pintype "power_in"))
      (node (ref "LED3") (pin "VDD") (pinfunction "VDD_VDD") (pintype "power_in"))
      (node (ref "LED30") (pin "VDD") (pinfunction "VDD_VDD") (pintype "power_in"))
      (node (ref "LED31") (pin "VDD") (pinfunction "VDD_VDD") (pintype "power_in"))
      (node (ref "LED32") (pin "VDD") (pinfunction "VDD_VDD") (pintype "power_in"))
      (node (ref "LED33") (pin "VDD") (pinfunction "VDD_VDD") (pintype "power_in"))
      (node (ref "LED34") (pin "VDD") (pinfunction "VDD_VDD") (pintype "power_in"))
      (node (ref "LED35") (pin "VDD") (pinfunction "VDD_VDD") (pintype "power_in"))
      (node (ref "LED36") (pin "VDD") (pinfunction "VDD_VDD") (pintype "power_in"))
      (node (ref "LED37") (pin "VDD") (pinfunction "VDD_VDD") (pintype "power_in"))
      (node (ref "LED38") (pin "VDD") (pinfunction "VDD_VDD") (pintype "power_in"))
      (node (ref "LED39") (pin "VDD") (pinfunction "VDD_VDD") (pintype "power_in"))
      (node (ref "LED4") (pin "VDD") (pinfunction "VDD_VDD") (pintype "power_in"))
      (node (ref "LED40") (pin "VDD") (pinfunction "VDD_VDD") (pintype "power_in"))
      (node (ref "LED41") (pin "VDD") (pinfunction "VDD_VDD") (pintype "power_in"))
      (node (ref "LED42") (pin "VDD") (pinfunction "VDD_VDD") (pintype "power_in"))
      (node (ref "LED43") (pin "VDD") (pinfunction "VDD_VDD") (pintype "power_in"))
      (node (ref "LED44") (pin "VDD") (pinfunction "VDD_VDD") (pintype "power_in"))
      (node (ref "LED45") (pin "VDD") (pinfunction "VDD_VDD") (pintype "power_in"))
      (node (ref "LED46") (pin "VDD") (pinfunction "VDD_VDD") (pintype "power_in"))
      (node (ref "LED47") (pin "VDD") (pinfunction "VDD_VDD") (pintype "power_in"))
      (node (ref "LED48") (pin "VDD") (pinfunction "VDD_VDD") (pintype "power_in"))
      (node (ref "LED49") (pin "VDD") (pinfunction "VDD_VDD") (pintype "power_in"))
      (node (ref "LED5") (pin "VDD") (pinfunction "VDD_VDD") (pintype "power_in"))
      (node (ref "LED50") (pin "VDD") (pinfunction "VDD_VDD") (pintype "power_in"))
      (node (ref "LED51") (pin "VDD") (pinfunction "VDD_VDD") (pintype "power_in"))
      (node (ref "LED52") (pin "VDD") (pinfunction "VDD_VDD") (pintype "power_in"))
      (node (ref "LED53") (pin "VDD") (pinfunction "VDD_VDD") (pintype "power_in"))
      (node (ref "LED54") (pin "VDD") (pinfunction "VDD_VDD") (pintype "power_in"))
      (node (ref "LED55") (pin "VDD") (pinfunction "VDD_VDD") (pintype "power_in"))
      (node (ref "LED56") (pin "VDD") (pinfunction "VDD_VDD") (pintype "power_in"))
      (node (ref "LED57") (pin "VDD") (pinfunction "VDD_VDD") (pintype "power_in"))
      (node (ref "LED58") (pin "VDD") (pinfunction "VDD_VDD") (pintype "power_in"))
      (node (ref "LED59") (pin "VDD") (pinfunction "VDD_VDD") (pintype "power_in"))
      (node (ref "LED6") (pin "VDD") (pinfunction "VDD_VDD") (pintype "power_in"))
      (node (ref "LED60") (pin "VDD") (pinfunction "VDD_VDD") (pintype "power_in"))
      (node (ref "LED7") (pin "VDD") (pinfunction "VDD_VDD") (pintype "power_in"))
      (node (ref "LED8") (pin "VDD") (pinfunction "VDD_VDD") (pintype "power_in"))
      (node (ref "LED9") (pin "VDD") (pinfunction "VDD_VDD") (pintype "power_in"))
      (node (ref "LTC4412") (pin "6") (pinfunction "SENSE_6") (pintype "bidirectional"))
      (node (ref "PUSHPULL") (pin "1") (pinfunction "1OE_1") (pintype "bidirectional"))
      (node (ref "PUSHPULL") (pin "14") (pinfunction "VCC_14") (pintype "bidirectional"))
      (node (ref "PUSHPULL") (pin "4") (pinfunction "2OE_4") (pintype "bidirectional"))
      (node (ref "R2") (pin "2") (pinfunction "2_2") (pintype "passive"))
      (node (ref "SI4465DY_1") (pin "1") (pinfunction "S_1") (pintype "passive"))
      (node (ref "SI4465DY_1") (pin "2") (pinfunction "S_2") (pintype "passive"))
      (node (ref "SI4465DY_1") (pin "3") (pinfunction "S_3") (pintype "passive"))
      (node (ref "SI4465DY_2") (pin "1") (pinfunction "S_1") (pintype "passive"))
      (node (ref "SI4465DY_2") (pin "2") (pinfunction "S_2") (pintype "passive"))
      (node (ref "SI4465DY_2") (pin "3") (pinfunction "S_3") (pintype "passive"))
    )
    (net (code "3") (name "D+") (class "Default")
      (node (ref "C70") (pin "2") (pinfunction "2_2") (pintype "passive"))
      (node (ref "MCU") (pin "71") (pinfunction "PA12_71") (pintype "bidirectional"))
      (node (ref "R4") (pin "2") (pinfunction "2_2") (pintype "passive"))
      (node (ref "R6") (pin "1") (pinfunction "1_1") (pintype "passive"))
    )
    (net (code "4") (name "D-") (class "Default")
      (node (ref "C69") (pin "2") (pinfunction "2_2") (pintype "passive"))
      (node (ref "MCU") (pin "70") (pinfunction "PA11_70") (pintype "bidirectional"))
      (node (ref "R5") (pin "2") (pinfunction "2_2") (pintype "passive"))
    )
    (net (code "5") (name "DATA_IN_1_HIGH") (class "Default")
      (node (ref "PUSHPULL") (pin "11") (pinfunction "4Y_11") (pintype "bidirectional"))
      (node (ref "R1") (pin "1") (pinfunction "1_1") (pintype "passive"))
    )
    (net (code "6") (name "DATA_IN_1_LOW") (class "Default")
      (node (ref "MCU") (pin "39") (pinfunction "PE9_39") (pintype "bidirectional"))
      (node (ref "PUSHPULL") (pin "12") (pinfunction "4A_12") (pintype "bidirectional"))
    )
    (net (code "7") (name "DATA_IN_2_HIGH") (class "Default")
      (node (ref "PUSHPULL") (pin "8") (pinfunction "3Y_8") (pintype "bidirectional"))
      (node (ref "R3") (pin "1") (pinfunction "1_1") (pintype "passive"))
    )
    (net (code "8") (name "DATA_IN_2_LOW") (class "Default")
      (node (ref "MCU") (pin "41") (pinfunction "PE11_41") (pintype "bidirectional"))
      (node (ref "PUSHPULL") (pin "9") (pinfunction "3A_9") (pintype "bidirectional"))
    )
    (net (code "9") (name "GND") (class "Default")
      (node (ref "C1") (pin "2") (pinfunction "2_2") (pintype "passive"))
      (node (ref "C10") (pin "2") (pinfunction "2_2") (pintype "passive"))
      (node (ref "C11") (pin "2") (pinfunction "2_2") (pintype "passive"))
      (node (ref "C12") (pin "2") (pinfunction "2_2") (pintype "passive"))
      (node (ref "C13") (pin "2") (pinfunction "2_2") (pintype "passive"))
      (node (ref "C14") (pin "2") (pinfunction "2_2") (pintype "passive"))
      (node (ref "C15") (pin "2") (pinfunction "2_2") (pintype "passive"))
      (node (ref "C16") (pin "2") (pinfunction "2_2") (pintype "passive"))
      (node (ref "C17") (pin "2") (pinfunction "2_2") (pintype "passive"))
      (node (ref "C18") (pin "2") (pinfunction "2_2") (pintype "passive"))
      (node (ref "C19") (pin "2") (pinfunction "2_2") (pintype "passive"))
      (node (ref "C2") (pin "2") (pinfunction "2_2") (pintype "passive"))
      (node (ref "C20") (pin "2") (pinfunction "2_2") (pintype "passive"))
      (node (ref "C21") (pin "2") (pinfunction "2_2") (pintype "passive"))
      (node (ref "C22") (pin "2") (pinfunction "2_2") (pintype "passive"))
      (node (ref "C23") (pin "2") (pinfunction "2_2") (pintype "passive"))
      (node (ref "C24") (pin "2") (pinfunction "2_2") (pintype "passive"))
      (node (ref "C25") (pin "2") (pinfunction "2_2") (pintype "passive"))
      (node (ref "C26") (pin "2") (pinfunction "2_2") (pintype "passive"))
      (node (ref "C27") (pin "2") (pinfunction "2_2") (pintype "passive"))
      (node (ref "C28") (pin "2") (pinfunction "2_2") (pintype "passive"))
      (node (ref "C29") (pin "2") (pinfunction "2_2") (pintype "passive"))
      (node (ref "C3") (pin "2") (pinfunction "2_2") (pintype "passive"))
      (node (ref "C30") (pin "2") (pinfunction "2_2") (pintype "passive"))
      (node (ref "C31") (pin "2") (pinfunction "2_2") (pintype "passive"))
      (node (ref "C32") (pin "2") (pinfunction "2_2") (pintype "passive"))
      (node (ref "C33") (pin "2") (pinfunction "2_2") (pintype "passive"))
      (node (ref "C34") (pin "2") (pinfunction "2_2") (pintype "passive"))
      (node (ref "C35") (pin "2") (pinfunction "2_2") (pintype "passive"))
      (node (ref "C36") (pin "2") (pinfunction "2_2") (pintype "passive"))
      (node (ref "C37") (pin "2") (pinfunction "2_2") (pintype "passive"))
      (node (ref "C38") (pin "2") (pinfunction "2_2") (pintype "passive"))
      (node (ref "C39") (pin "2") (pinfunction "2_2") (pintype "passive"))
      (node (ref "C4") (pin "2") (pinfunction "2_2") (pintype "passive"))
      (node (ref "C40") (pin "2") (pinfunction "2_2") (pintype "passive"))
      (node (ref "C41") (pin "2") (pinfunction "2_2") (pintype "passive"))
      (node (ref "C42") (pin "2") (pinfunction "2_2") (pintype "passive"))
      (node (ref "C43") (pin "2") (pinfunction "2_2") (pintype "passive"))
      (node (ref "C44") (pin "2") (pinfunction "2_2") (pintype "passive"))
      (node (ref "C45") (pin "2") (pinfunction "2_2") (pintype "passive"))
      (node (ref "C46") (pin "2") (pinfunction "2_2") (pintype "passive"))
      (node (ref "C47") (pin "2") (pinfunction "2_2") (pintype "passive"))
      (node (ref "C48") (pin "2") (pinfunction "2_2") (pintype "passive"))
      (node (ref "C49") (pin "2") (pinfunction "2_2") (pintype "passive"))
      (node (ref "C5") (pin "2") (pinfunction "2_2") (pintype "passive"))
      (node (ref "C50") (pin "2") (pinfunction "2_2") (pintype "passive"))
      (node (ref "C51") (pin "2") (pinfunction "2_2") (pintype "passive"))
      (node (ref "C52") (pin "2") (pinfunction "2_2") (pintype "passive"))
      (node (ref "C53") (pin "2") (pinfunction "2_2") (pintype "passive"))
      (node (ref "C54") (pin "2") (pinfunction "2_2") (pintype "passive"))
      (node (ref "C55") (pin "2") (pinfunction "2_2") (pintype "passive"))
      (node (ref "C56") (pin "2") (pinfunction "2_2") (pintype "passive"))
      (node (ref "C57") (pin "2") (pinfunction "2_2") (pintype "passive"))
      (node (ref "C58") (pin "2") (pinfunction "2_2") (pintype "passive"))
      (node (ref "C59") (pin "2") (pinfunction "2_2") (pintype "passive"))
      (node (ref "C6") (pin "2") (pinfunction "2_2") (pintype "passive"))
      (node (ref "C60") (pin "2") (pinfunction "2_2") (pintype "passive"))
      (node (ref "C61") (pin "2") (pinfunction "2_2") (pintype "passive"))
      (node (ref "C62") (pin "2") (pinfunction "2_2") (pintype "passive"))
      (node (ref "C63") (pin "2") (pinfunction "2_2") (pintype "passive"))
      (node (ref "C64") (pin "2") (pinfunction "2_2") (pintype "passive"))
      (node (ref "C65") (pin "2") (pinfunction "2_2") (pintype "passive"))
      (node (ref "C66") (pin "2") (pinfunction "2_2") (pintype "passive"))
      (node (ref "C67") (pin "1") (pinfunction "1_1") (pintype "passive"))
      (node (ref "C68") (pin "1") (pinfunction "1_1") (pintype "passive"))
      (node (ref "C69") (pin "1") (pinfunction "1_1") (pintype "passive"))
      (node (ref "C7") (pin "2") (pinfunction "2_2") (pintype "passive"))
      (node (ref "C70") (pin "1") (pinfunction "1_1") (pintype "passive"))
      (node (ref "C71") (pin "2") (pinfunction "2_2") (pintype "passive"))
      (node (ref "C72") (pin "2") (pinfunction "2_2") (pintype "passive"))
      (node (ref "C73") (pin "2") (pinfunction "2_2") (pintype "passive"))
      (node (ref "C74") (pin "2") (pinfunction "2_2") (pintype "passive"))
      (node (ref "C75") (pin "2") (pinfunction "2_2") (pintype "passive"))
      (node (ref "C8") (pin "2") (pinfunction "2_2") (pintype "passive"))
      (node (ref "C9") (pin "2") (pinfunction "2_2") (pintype "passive"))
      (node (ref "D1") (pin "2") (pinfunction "GND_2") (pintype "power_in"))
      (node (ref "JP1") (pin "10") (pinfunction "10_10") (pintype "passive"))
      (node (ref "JP1") (pin "12") (pinfunction "12_12") (pintype "passive"))
      (node (ref "JP1") (pin "14") (pinfunction "14_14") (pintype "passive"))
      (node (ref "JP1") (pin "16") (pinfunction "16_16") (pintype "passive"))
      (node (ref "JP1") (pin "18") (pinfunction "18_18") (pintype "passive"))
      (node (ref "JP1") (pin "20") (pinfunction "20_20") (pintype "passive"))
      (node (ref "JP1") (pin "4") (pinfunction "4_4") (pintype "passive"))
      (node (ref "JP1") (pin "6") (pinfunction "6_6") (pintype "passive"))
      (node (ref "JP1") (pin "8") (pinfunction "8_8") (pintype "passive"))
      (node (ref "K1") (pin "2") (pinfunction "2_2") (pintype "passive"))
      (node (ref "K1") (pin "3") (pinfunction "3_3") (pintype "passive"))
      (node (ref "LDO") (pin "2") (pinfunction "GND_2") (pintype "bidirectional"))
      (node (ref "LED1") (pin "VSS") (pinfunction "GND_VSS") (pintype "power_in"))
      (node (ref "LED10") (pin "VSS") (pinfunction "GND_VSS") (pintype "power_in"))
      (node (ref "LED11") (pin "VSS") (pinfunction "GND_VSS") (pintype "power_in"))
      (node (ref "LED12") (pin "VSS") (pinfunction "GND_VSS") (pintype "power_in"))
      (node (ref "LED13") (pin "VSS") (pinfunction "GND_VSS") (pintype "power_in"))
      (node (ref "LED14") (pin "VSS") (pinfunction "GND_VSS") (pintype "power_in"))
      (node (ref "LED15") (pin "VSS") (pinfunction "GND_VSS") (pintype "power_in"))
      (node (ref "LED16") (pin "VSS") (pinfunction "GND_VSS") (pintype "power_in"))
      (node (ref "LED17") (pin "VSS") (pinfunction "GND_VSS") (pintype "power_in"))
      (node (ref "LED18") (pin "VSS") (pinfunction "GND_VSS") (pintype "power_in"))
      (node (ref "LED19") (pin "VSS") (pinfunction "GND_VSS") (pintype "power_in"))
      (node (ref "LED2") (pin "VSS") (pinfunction "GND_VSS") (pintype "power_in"))
      (node (ref "LED20") (pin "VSS") (pinfunction "GND_VSS") (pintype "power_in"))
      (node (ref "LED21") (pin "VSS") (pinfunction "GND_VSS") (pintype "power_in"))
      (node (ref "LED22") (pin "VSS") (pinfunction "GND_VSS") (pintype "power_in"))
      (node (ref "LED23") (pin "VSS") (pinfunction "GND_VSS") (pintype "power_in"))
      (node (ref "LED24") (pin "VSS") (pinfunction "GND_VSS") (pintype "power_in"))
      (node (ref "LED25") (pin "VSS") (pinfunction "GND_VSS") (pintype "power_in"))
      (node (ref "LED26") (pin "VSS") (pinfunction "GND_VSS") (pintype "power_in"))
      (node (ref "LED27") (pin "VSS") (pinfunction "GND_VSS") (pintype "power_in"))
      (node (ref "LED28") (pin "VSS") (pinfunction "GND_VSS") (pintype "power_in"))
      (node (ref "LED29") (pin "VSS") (pinfunction "GND_VSS") (pintype "power_in"))
      (node (ref "LED3") (pin "VSS") (pinfunction "GND_VSS") (pintype "power_in"))
      (node (ref "LED30") (pin "VSS") (pinfunction "GND_VSS") (pintype "power_in"))
      (node (ref "LED31") (pin "VSS") (pinfunction "GND_VSS") (pintype "power_in"))
      (node (ref "LED32") (pin "VSS") (pinfunction "GND_VSS") (pintype "power_in"))
      (node (ref "LED33") (pin "VSS") (pinfunction "GND_VSS") (pintype "power_in"))
      (node (ref "LED34") (pin "VSS") (pinfunction "GND_VSS") (pintype "power_in"))
      (node (ref "LED35") (pin "VSS") (pinfunction "GND_VSS") (pintype "power_in"))
      (node (ref "LED36") (pin "VSS") (pinfunction "GND_VSS") (pintype "power_in"))
      (node (ref "LED37") (pin "VSS") (pinfunction "GND_VSS") (pintype "power_in"))
      (node (ref "LED38") (pin "VSS") (pinfunction "GND_VSS") (pintype "power_in"))
      (node (ref "LED39") (pin "VSS") (pinfunction "GND_VSS") (pintype "power_in"))
      (node (ref "LED4") (pin "VSS") (pinfunction "GND_VSS") (pintype "power_in"))
      (node (ref "LED40") (pin "VSS") (pinfunction "GND_VSS") (pintype "power_in"))
      (node (ref "LED41") (pin "VSS") (pinfunction "GND_VSS") (pintype "power_in"))
      (node (ref "LED42") (pin "VSS") (pinfunction "GND_VSS") (pintype "power_in"))
      (node (ref "LED43") (pin "VSS") (pinfunction "GND_VSS") (pintype "power_in"))
      (node (ref "LED44") (pin "VSS") (pinfunction "GND_VSS") (pintype "power_in"))
      (node (ref "LED45") (pin "VSS") (pinfunction "GND_VSS") (pintype "power_in"))
      (node (ref "LED46") (pin "VSS") (pinfunction "GND_VSS") (pintype "power_in"))
      (node (ref "LED47") (pin "VSS") (pinfunction "GND_VSS") (pintype "power_in"))
      (node (ref "LED48") (pin "VSS") (pinfunction "GND_VSS") (pintype "power_in"))
      (node (ref "LED49") (pin "VSS") (pinfunction "GND_VSS") (pintype "power_in"))
      (node (ref "LED5") (pin "VSS") (pinfunction "GND_VSS") (pintype "power_in"))
      (node (ref "LED50") (pin "VSS") (pinfunction "GND_VSS") (pintype "power_in"))
      (node (ref "LED51") (pin "VSS") (pinfunction "GND_VSS") (pintype "power_in"))
      (node (ref "LED52") (pin "VSS") (pinfunction "GND_VSS") (pintype "power_in"))
      (node (ref "LED53") (pin "VSS") (pinfunction "GND_VSS") (pintype "power_in"))
      (node (ref "LED54") (pin "VSS") (pinfunction "GND_VSS") (pintype "power_in"))
      (node (ref "LED55") (pin "VSS") (pinfunction "GND_VSS") (pintype "power_in"))
      (node (ref "LED56") (pin "VSS") (pinfunction "GND_VSS") (pintype "power_in"))
      (node (ref "LED57") (pin "VSS") (pinfunction "GND_VSS") (pintype "power_in"))
      (node (ref "LED58") (pin "VSS") (pinfunction "GND_VSS") (pintype "power_in"))
      (node (ref "LED59") (pin "VSS") (pinfunction "GND_VSS") (pintype "power_in"))
      (node (ref "LED6") (pin "VSS") (pinfunction "GND_VSS") (pintype "power_in"))
      (node (ref "LED60") (pin "VSS") (pinfunction "GND_VSS") (pintype "power_in"))
      (node (ref "LED7") (pin "VSS") (pinfunction "GND_VSS") (pintype "power_in"))
      (node (ref "LED8") (pin "VSS") (pinfunction "GND_VSS") (pintype "power_in"))
      (node (ref "LED9") (pin "VSS") (pinfunction "GND_VSS") (pintype "power_in"))
      (node (ref "LTC4412") (pin "2") (pinfunction "GND_2") (pintype "bidirectional"))
      (node (ref "LTC4412") (pin "3") (pinfunction "CTL_3") (pintype "bidirectional"))
      (node (ref "MCU") (pin "10") (pinfunction "VSS1_10") (pintype "power_in"))
      (node (ref "MCU") (pin "19") (pinfunction "VSSA_19") (pintype "power_in"))
      (node (ref "MCU") (pin "26") (pinfunction "VSS2_26") (pintype "power_in"))
      (node (ref "MCU") (pin "49") (pinfunction "VSS3_49") (pintype "power_in"))
      (node (ref "MCU") (pin "74") (pinfunction "VSS4_74") (pintype "power_in"))
      (node (ref "MCU") (pin "99") (pinfunction "VSS5_99") (pintype "power_in"))
      (node (ref "PUSHPULL") (pin "10") (pinfunction "3OE_10") (pintype "bidirectional"))
      (node (ref "PUSHPULL") (pin "13") (pinfunction "4OE_13") (pintype "bidirectional"))
      (node (ref "PUSHPULL") (pin "3") (pinfunction "1Y_3") (pintype "bidirectional"))
      (node (ref "PUSHPULL") (pin "6") (pinfunction "2Y_6") (pintype "bidirectional"))
      (node (ref "PUSHPULL") (pin "7") (pinfunction "GND_7") (pintype "bidirectional"))
      (node (ref "R6") (pin "2") (pinfunction "2_2") (pintype "passive"))
      (node (ref "R7") (pin "2") (pinfunction "2_2") (pintype "passive"))
      (node (ref "R8") (pin "2") (pinfunction "2_2") (pintype "passive"))
      (node (ref "R9") (pin "2") (pinfunction "2_2") (pintype "passive"))
      (node (ref "X1") (pin "GND") (pinfunction "GND_GND") (pintype "bidirectional"))
    )
    (net (code "10") (name "JTCK") (class "Default")
      (node (ref "JP1") (pin "9") (pinfunction "9_9") (pintype "passive"))
      (node (ref "MCU") (pin "76") (pinfunction "PA14_76") (pintype "bidirectional"))
    )
    (net (code "11") (name "JTDI") (class "Default")
      (node (ref "JP1") (pin "5") (pinfunction "5_5") (pintype "passive"))
      (node (ref "MCU") (pin "77") (pinfunction "PA15_77") (pintype "bidirectional"))
    )
    (net (code "12") (name "JTDO") (class "Default")
      (node (ref "JP1") (pin "13") (pinfunction "13_13") (pintype "passive"))
      (node (ref "MCU") (pin "89") (pinfunction "PB3_89") (pintype "bidirectional"))
    )
    (net (code "13") (name "JTMS") (class "Default")
      (node (ref "JP1") (pin "7") (pinfunction "7_7") (pintype "passive"))
      (node (ref "MCU") (pin "72") (pinfunction "PA13_72") (pintype "bidirectional"))
    )
    (net (code "14") (name "NJTRST") (class "Default")
      (node (ref "JP1") (pin "3") (pinfunction "3_3") (pintype "passive"))
      (node (ref "MCU") (pin "90") (pinfunction "PB4_90") (pintype "bidirectional"))
    )
    (net (code "15") (name "NRSTIN") (class "Default")
      (node (ref "JP1") (pin "15") (pinfunction "15_15") (pintype "passive"))
      (node (ref "MCU") (pin "14") (pinfunction "NRST_14") (pintype "bidirectional"))
    )
    (net (code "16") (name "Net-(D1-2)") (class "Default")
      (node (ref "D1") (pin "3") (pinfunction "2_3") (pintype "passive"))
      (node (ref "L1") (pin "2") (pinfunction "3_2") (pintype "passive"))
    )
    (net (code "17") (name "Net-(D1-3)") (class "Default")
      (node (ref "D1") (pin "4") (pinfunction "3_4") (pintype "passive"))
      (node (ref "R5") (pin "1") (pinfunction "1_1") (pintype "passive"))
    )
    (net (code "18") (name "Net-(D1-4)") (class "Default")
      (node (ref "D1") (pin "6") (pinfunction "4_6") (pintype "passive"))
      (node (ref "R4") (pin "1") (pinfunction "1_1") (pintype "passive"))
    )
    (net (code "19") (name "Net-(D3-C)") (class "Default")
      (node (ref "D3") (pin "1") (pinfunction "C_1") (pintype "passive"))
      (node (ref "SI4465DY_1") (pin "5") (pinfunction "D_5") (pintype "passive"))
      (node (ref "SI4465DY_1") (pin "6") (pinfunction "D_6") (pintype "passive"))
      (node (ref "SI4465DY_1") (pin "7") (pinfunction "D_7") (pintype "passive"))
      (node (ref "SI4465DY_1") (pin "8") (pinfunction "D_8") (pintype "passive"))
    )
    (net (code "20") (name "Net-(JP1-Pad11)") (class "Default")
      (node (ref "JP1") (pin "11") (pinfunction "11_11") (pintype "passive"))
      (node (ref "R9") (pin "1") (pinfunction "1_1") (pintype "passive"))
    )
    (net (code "21") (name "Net-(JP1-Pad17)") (class "Default")
      (node (ref "JP1") (pin "17") (pinfunction "17_17") (pintype "passive"))
      (node (ref "R8") (pin "1") (pinfunction "1_1") (pintype "passive"))
    )
    (net (code "22") (name "Net-(JP1-Pad19)") (class "Default")
      (node (ref "JP1") (pin "19") (pinfunction "19_19") (pintype "passive"))
      (node (ref "R7") (pin "1") (pinfunction "1_1") (pintype "passive"))
    )
    (net (code "23") (name "Net-(L1-1)") (class "Default")
      (node (ref "L1") (pin "4") (pinfunction "1_4") (pintype "passive"))
      (node (ref "X1") (pin "D+") (pinfunction "D+_D+") (pintype "bidirectional"))
    )
    (net (code "24") (name "Net-(L1-2)") (class "Default")
      (node (ref "D1") (pin "1") (pinfunction "1_1") (pintype "passive"))
      (node (ref "L1") (pin "3") (pinfunction "2_3") (pintype "passive"))
    )
    (net (code "25") (name "Net-(L1-4)") (class "Default")
      (node (ref "L1") (pin "1") (pinfunction "4_1") (pintype "passive"))
      (node (ref "X1") (pin "D-") (pinfunction "D-_D-") (pintype "bidirectional"))
    )
    (net (code "26") (name "Net-(LDO-OUT)") (class "Default")
      (node (ref "C66") (pin "1") (pinfunction "1_1") (pintype "passive"))
      (node (ref "FERRITBEAD") (pin "1") (pinfunction "1_1") (pintype "passive"))
      (node (ref "LDO") (pin "5") (pinfunction "OUT_5") (pintype "bidirectional"))
    )
    (net (code "27") (name "Net-(LED1-DI)") (class "Default")
      (node (ref "LED1") (pin "DIN") (pinfunction "DI_DIN") (pintype "input"))
      (node (ref "LED30") (pin "DOUT") (pinfunction "DO_DOUT") (pintype "output"))
    )
    (net (code "28") (name "Net-(LED1-DO)") (class "Default")
      (node (ref "LED1") (pin "DOUT") (pinfunction "DO_DOUT") (pintype "output"))
      (node (ref "LED2") (pin "DIN") (pinfunction "DI_DIN") (pintype "input"))
    )
    (net (code "29") (name "Net-(LED2-DO)") (class "Default")
      (node (ref "LED2") (pin "DOUT") (pinfunction "DO_DOUT") (pintype "output"))
      (node (ref "LED3") (pin "DIN") (pinfunction "DI_DIN") (pintype "input"))
    )
    (net (code "30") (name "Net-(LED3-DO)") (class "Default")
      (node (ref "LED3") (pin "DOUT") (pinfunction "DO_DOUT") (pintype "output"))
      (node (ref "LED4") (pin "DIN") (pinfunction "DI_DIN") (pintype "input"))
    )
    (net (code "31") (name "Net-(LED4-DO)") (class "Default")
      (node (ref "LED4") (pin "DOUT") (pinfunction "DO_DOUT") (pintype "output"))
      (node (ref "LED5") (pin "DIN") (pinfunction "DI_DIN") (pintype "input"))
    )
    (net (code "32") (name "Net-(LED5-DO)") (class "Default")
      (node (ref "LED5") (pin "DOUT") (pinfunction "DO_DOUT") (pintype "output"))
      (node (ref "LED6") (pin "DIN") (pinfunction "DI_DIN") (pintype "input"))
    )
    (net (code "33") (name "Net-(LED6-DO)") (class "Default")
      (node (ref "LED6") (pin "DOUT") (pinfunction "DO_DOUT") (pintype "output"))
      (node (ref "LED7") (pin "DIN") (pinfunction "DI_DIN") (pintype "input"))
    )
    (net (code "34") (name "Net-(LED7-DO)") (class "Default")
      (node (ref "LED7") (pin "DOUT") (pinfunction "DO_DOUT") (pintype "output"))
      (node (ref "LED8") (pin "DIN") (pinfunction "DI_DIN") (pintype "input"))
    )
    (net (code "35") (name "Net-(LED8-DO)") (class "Default")
      (node (ref "LED8") (pin "DOUT") (pinfunction "DO_DOUT") (pintype "output"))
      (node (ref "LED9") (pin "DIN") (pinfunction "DI_DIN") (pintype "input"))
    )
    (net (code "36") (name "Net-(LED10-DI)") (class "Default")
      (node (ref "LED10") (pin "DIN") (pinfunction "DI_DIN") (pintype "input"))
      (node (ref "LED9") (pin "DOUT") (pinfunction "DO_DOUT") (pintype "output"))
    )
    (net (code "37") (name "Net-(LED10-DO)") (class "Default")
      (node (ref "LED10") (pin "DOUT") (pinfunction "DO_DOUT") (pintype "output"))
      (node (ref "LED11") (pin "DIN") (pinfunction "DI_DIN") (pintype "input"))
    )
    (net (code "38") (name "Net-(LED11-DO)") (class "Default")
      (node (ref "LED11") (pin "DOUT") (pinfunction "DO_DOUT") (pintype "output"))
      (node (ref "LED12") (pin "DIN") (pinfunction "DI_DIN") (pintype "input"))
    )
    (net (code "39") (name "Net-(LED12-DO)") (class "Default")
      (node (ref "LED12") (pin "DOUT") (pinfunction "DO_DOUT") (pintype "output"))
      (node (ref "LED13") (pin "DIN") (pinfunction "DI_DIN") (pintype "input"))
    )
    (net (code "40") (name "Net-(LED13-DO)") (class "Default")
      (node (ref "LED13") (pin "DOUT") (pinfunction "DO_DOUT") (pintype "output"))
      (node (ref "LED14") (pin "DIN") (pinfunction "DI_DIN") (pintype "input"))
    )
    (net (code "41") (name "Net-(LED14-DO)") (class "Default")
      (node (ref "LED14") (pin "DOUT") (pinfunction "DO_DOUT") (pintype "output"))
      (node (ref "LED15") (pin "DIN") (pinfunction "DI_DIN") (pintype "input"))
    )
    (net (code "42") (name "Net-(LED16-DI)") (class "Default")
      (node (ref "LED16") (pin "DIN") (pinfunction "DI_DIN") (pintype "input"))
      (node (ref "R3") (pin "2") (pinfunction "2_2") (pintype "passive"))
    )
    (net (code "43") (name "Net-(LED16-DO)") (class "Default")
      (node (ref "LED16") (pin "DOUT") (pinfunction "DO_DOUT") (pintype "output"))
      (node (ref "LED17") (pin "DIN") (pinfunction "DI_DIN") (pintype "input"))
    )
    (net (code "44") (name "Net-(LED17-DO)") (class "Default")
      (node (ref "LED17") (pin "DOUT") (pinfunction "DO_DOUT") (pintype "output"))
      (node (ref "LED18") (pin "DIN") (pinfunction "DI_DIN") (pintype "input"))
    )
    (net (code "45") (name "Net-(LED18-DO)") (class "Default")
      (node (ref "LED18") (pin "DOUT") (pinfunction "DO_DOUT") (pintype "output"))
      (node (ref "LED19") (pin "DIN") (pinfunction "DI_DIN") (pintype "input"))
    )
    (net (code "46") (name "Net-(LED19-DO)") (class "Default")
      (node (ref "LED19") (pin "DOUT") (pinfunction "DO_DOUT") (pintype "output"))
      (node (ref "LED20") (pin "DIN") (pinfunction "DI_DIN") (pintype "input"))
    )
    (net (code "47") (name "Net-(LED20-DO)") (class "Default")
      (node (ref "LED20") (pin "DOUT") (pinfunction "DO_DOUT") (pintype "output"))
      (node (ref "LED21") (pin "DIN") (pinfunction "DI_DIN") (pintype "input"))
    )
    (net (code "48") (name "Net-(LED21-DO)") (class "Default")
      (node (ref "LED21") (pin "DOUT") (pinfunction "DO_DOUT") (pintype "output"))
      (node (ref "LED22") (pin "DIN") (pinfunction "DI_DIN") (pintype "input"))
    )
    (net (code "49") (name "Net-(LED22-DO)") (class "Default")
      (node (ref "LED22") (pin "DOUT") (pinfunction "DO_DOUT") (pintype "output"))
      (node (ref "LED23") (pin "DIN") (pinfunction "DI_DIN") (pintype "input"))
    )
    (net (code "50") (name "Net-(LED23-DO)") (class "Default")
      (node (ref "LED23") (pin "DOUT") (pinfunction "DO_DOUT") (pintype "output"))
      (node (ref "LED24") (pin "DIN") (pinfunction "DI_DIN") (pintype "input"))
    )
    (net (code "51") (name "Net-(LED24-DO)") (class "Default")
      (node (ref "LED24") (pin "DOUT") (pinfunction "DO_DOUT") (pintype "output"))
      (node (ref "LED25") (pin "DIN") (pinfunction "DI_DIN") (pintype "input"))
    )
    (net (code "52") (name "Net-(LED25-DO)") (class "Default")
      (node (ref "LED25") (pin "DOUT") (pinfunction "DO_DOUT") (pintype "output"))
      (node (ref "LED26") (pin "DIN") (pinfunction "DI_DIN") (pintype "input"))
    )
    (net (code "53") (name "Net-(LED26-DO)") (class "Default")
      (node (ref "LED26") (pin "DOUT") (pinfunction "DO_DOUT") (pintype "output"))
      (node (ref "LED27") (pin "DIN") (pinfunction "DI_DIN") (pintype "input"))
    )
    (net (code "54") (name "Net-(LED27-DO)") (class "Default")
      (node (ref "LED27") (pin "DOUT") (pinfunction "DO_DOUT") (pintype "output"))
      (node (ref "LED28") (pin "DIN") (pinfunction "DI_DIN") (pintype "input"))
    )
    (net (code "55") (name "Net-(LED28-DO)") (class "Default")
      (node (ref "LED28") (pin "DOUT") (pinfunction "DO_DOUT") (pintype "output"))
      (node (ref "LED29") (pin "DIN") (pinfunction "DI_DIN") (pintype "input"))
    )
    (net (code "56") (name "Net-(LED29-DO)") (class "Default")
      (node (ref "LED29") (pin "DOUT") (pinfunction "DO_DOUT") (pintype "output"))
      (node (ref "LED30") (pin "DIN") (pinfunction "DI_DIN") (pintype "input"))
    )
    (net (code "57") (name "Net-(LED31-DI)") (class "Default")
      (node (ref "LED31") (pin "DIN") (pinfunction "DI_DIN") (pintype "input"))
      (node (ref "LED60") (pin "DOUT") (pinfunction "DO_DOUT") (pintype "output"))
    )
    (net (code "58") (name "Net-(LED31-DO)") (class "Default")
      (node (ref "LED31") (pin "DOUT") (pinfunction "DO_DOUT") (pintype "output"))
      (node (ref "LED32") (pin "DIN") (pinfunction "DI_DIN") (pintype "input"))
    )
    (net (code "59") (name "Net-(LED32-DO)") (class "Default")
      (node (ref "LED32") (pin "DOUT") (pinfunction "DO_DOUT") (pintype "output"))
      (node (ref "LED33") (pin "DIN") (pinfunction "DI_DIN") (pintype "input"))
    )
    (net (code "60") (name "Net-(LED33-DO)") (class "Default")
      (node (ref "LED33") (pin "DOUT") (pinfunction "DO_DOUT") (pintype "output"))
      (node (ref "LED34") (pin "DIN") (pinfunction "DI_DIN") (pintype "input"))
    )
    (net (code "61") (name "Net-(LED34-DO)") (class "Default")
      (node (ref "LED34") (pin "DOUT") (pinfunction "DO_DOUT") (pintype "output"))
      (node (ref "LED35") (pin "DIN") (pinfunction "DI_DIN") (pintype "input"))
    )
    (net (code "62") (name "Net-(LED35-DO)") (class "Default")
      (node (ref "LED35") (pin "DOUT") (pinfunction "DO_DOUT") (pintype "output"))
      (node (ref "LED36") (pin "DIN") (pinfunction "DI_DIN") (pintype "input"))
    )
    (net (code "63") (name "Net-(LED36-DO)") (class "Default")
      (node (ref "LED36") (pin "DOUT") (pinfunction "DO_DOUT") (pintype "output"))
      (node (ref "LED37") (pin "DIN") (pinfunction "DI_DIN") (pintype "input"))
    )
    (net (code "64") (name "Net-(LED37-DO)") (class "Default")
      (node (ref "LED37") (pin "DOUT") (pinfunction "DO_DOUT") (pintype "output"))
      (node (ref "LED38") (pin "DIN") (pinfunction "DI_DIN") (pintype "input"))
    )
    (net (code "65") (name "Net-(LED38-DO)") (class "Default")
      (node (ref "LED38") (pin "DOUT") (pinfunction "DO_DOUT") (pintype "output"))
      (node (ref "LED39") (pin "DIN") (pinfunction "DI_DIN") (pintype "input"))
    )
    (net (code "66") (name "Net-(LED39-DO)") (class "Default")
      (node (ref "LED39") (pin "DOUT") (pinfunction "DO_DOUT") (pintype "output"))
      (node (ref "LED40") (pin "DIN") (pinfunction "DI_DIN") (pintype "input"))
    )
    (net (code "67") (name "Net-(LED40-DO)") (class "Default")
      (node (ref "LED40") (pin "DOUT") (pinfunction "DO_DOUT") (pintype "output"))
      (node (ref "LED41") (pin "DIN") (pinfunction "DI_DIN") (pintype "input"))
    )
    (net (code "68") (name "Net-(LED41-DO)") (class "Default")
      (node (ref "LED41") (pin "DOUT") (pinfunction "DO_DOUT") (pintype "output"))
      (node (ref "LED42") (pin "DIN") (pinfunction "DI_DIN") (pintype "input"))
    )
    (net (code "69") (name "Net-(LED42-DO)") (class "Default")
      (node (ref "LED42") (pin "DOUT") (pinfunction "DO_DOUT") (pintype "output"))
      (node (ref "LED43") (pin "DIN") (pinfunction "DI_DIN") (pintype "input"))
    )
    (net (code "70") (name "Net-(LED43-DO)") (class "Default")
      (node (ref "LED43") (pin "DOUT") (pinfunction "DO_DOUT") (pintype "output"))
      (node (ref "LED44") (pin "DIN") (pinfunction "DI_DIN") (pintype "input"))
    )
    (net (code "71") (name "Net-(LED44-DO)") (class "Default")
      (node (ref "LED44") (pin "DOUT") (pinfunction "DO_DOUT") (pintype "output"))
      (node (ref "LED45") (pin "DIN") (pinfunction "DI_DIN") (pintype "input"))
    )
    (net (code "72") (name "Net-(LED46-DI)") (class "Default")
      (node (ref "LED46") (pin "DIN") (pinfunction "DI_DIN") (pintype "input"))
      (node (ref "R1") (pin "2") (pinfunction "2_2") (pintype "passive"))
    )
    (net (code "73") (name "Net-(LED46-DO)") (class "Default")
      (node (ref "LED46") (pin "DOUT") (pinfunction "DO_DOUT") (pintype "output"))
      (node (ref "LED47") (pin "DIN") (pinfunction "DI_DIN") (pintype "input"))
    )
    (net (code "74") (name "Net-(LED47-DO)") (class "Default")
      (node (ref "LED47") (pin "DOUT") (pinfunction "DO_DOUT") (pintype "output"))
      (node (ref "LED48") (pin "DIN") (pinfunction "DI_DIN") (pintype "input"))
    )
    (net (code "75") (name "Net-(LED48-DO)") (class "Default")
      (node (ref "LED48") (pin "DOUT") (pinfunction "DO_DOUT") (pintype "output"))
      (node (ref "LED49") (pin "DIN") (pinfunction "DI_DIN") (pintype "input"))
    )
    (net (code "76") (name "Net-(LED49-DO)") (class "Default")
      (node (ref "LED49") (pin "DOUT") (pinfunction "DO_DOUT") (pintype "output"))
      (node (ref "LED50") (pin "DIN") (pinfunction "DI_DIN") (pintype "input"))
    )
    (net (code "77") (name "Net-(LED50-DO)") (class "Default")
      (node (ref "LED50") (pin "DOUT") (pinfunction "DO_DOUT") (pintype "output"))
      (node (ref "LED51") (pin "DIN") (pinfunction "DI_DIN") (pintype "input"))
    )
    (net (code "78") (name "Net-(LED51-DO)") (class "Default")
      (node (ref "LED51") (pin "DOUT") (pinfunction "DO_DOUT") (pintype "output"))
      (node (ref "LED52") (pin "DIN") (pinfunction "DI_DIN") (pintype "input"))
    )
    (net (code "79") (name "Net-(LED52-DO)") (class "Default")
      (node (ref "LED52") (pin "DOUT") (pinfunction "DO_DOUT") (pintype "output"))
      (node (ref "LED53") (pin "DIN") (pinfunction "DI_DIN") (pintype "input"))
    )
    (net (code "80") (name "Net-(LED53-DO)") (class "Default")
      (node (ref "LED53") (pin "DOUT") (pinfunction "DO_DOUT") (pintype "output"))
      (node (ref "LED54") (pin "DIN") (pinfunction "DI_DIN") (pintype "input"))
    )
    (net (code "81") (name "Net-(LED54-DO)") (class "Default")
      (node (ref "LED54") (pin "DOUT") (pinfunction "DO_DOUT") (pintype "output"))
      (node (ref "LED55") (pin "DIN") (pinfunction "DI_DIN") (pintype "input"))
    )
    (net (code "82") (name "Net-(LED55-DO)") (class "Default")
      (node (ref "LED55") (pin "DOUT") (pinfunction "DO_DOUT") (pintype "output"))
      (node (ref "LED56") (pin "DIN") (pinfunction "DI_DIN") (pintype "input"))
    )
    (net (code "83") (name "Net-(LED56-DO)") (class "Default")
      (node (ref "LED56") (pin "DOUT") (pinfunction "DO_DOUT") (pintype "output"))
      (node (ref "LED57") (pin "DIN") (pinfunction "DI_DIN") (pintype "input"))
    )
    (net (code "84") (name "Net-(LED57-DO)") (class "Default")
      (node (ref "LED57") (pin "DOUT") (pinfunction "DO_DOUT") (pintype "output"))
      (node (ref "LED58") (pin "DIN") (pinfunction "DI_DIN") (pintype "input"))
    )
    (net (code "85") (name "Net-(LED58-DO)") (class "Default")
      (node (ref "LED58") (pin "DOUT") (pinfunction "DO_DOUT") (pintype "output"))
      (node (ref "LED59") (pin "DIN") (pinfunction "DI_DIN") (pintype "input"))
    )
    (net (code "86") (name "Net-(LED59-DO)") (class "Default")
      (node (ref "LED59") (pin "DOUT") (pinfunction "DO_DOUT") (pintype "output"))
      (node (ref "LED60") (pin "DIN") (pinfunction "DI_DIN") (pintype "input"))
    )
    (net (code "87") (name "Net-(LTC4412-GATE)") (class "Default")
      (node (ref "LTC4412") (pin "5") (pinfunction "GATE_5") (pintype "bidirectional"))
      (node (ref "SI4465DY_2") (pin "4") (pinfunction "G_4") (pintype "passive"))
    )
    (net (code "88") (name "OSC_IN") (class "Default")
      (node (ref "C74") (pin "1") (pinfunction "1_1") (pintype "passive"))
      (node (ref "MCU") (pin "12") (pinfunction "PH0-OSC_IN_12") (pintype "bidirectional"))
      (node (ref "Q1_24MHZ") (pin "1") (pinfunction "1_1") (pintype "passive"))
    )
    (net (code "89") (name "OSC_OUT") (class "Default")
      (node (ref "C75") (pin "1") (pinfunction "1_1") (pintype "passive"))
      (node (ref "MCU") (pin "13") (pinfunction "PH1-OSC_OUT_13") (pintype "bidirectional"))
      (node (ref "Q1_24MHZ") (pin "2") (pinfunction "2_2") (pintype "passive"))
    )
    (net (code "90") (name "PM_STATUS") (class "Default")
      (node (ref "LTC4412") (pin "4") (pinfunction "STAT_4") (pintype "bidirectional"))
      (node (ref "MCU") (pin "23") (pinfunction "PA1_23") (pintype "bidirectional"))
      (node (ref "R2") (pin "1") (pinfunction "1_1") (pintype "passive"))
      (node (ref "SI4465DY_1") (pin "4") (pinfunction "G_4") (pintype "passive"))
    )
    (net (code "91") (name "VBUS") (class "Default")
      (node (ref "C67") (pin "2") (pinfunction "2_2") (pintype "passive"))
      (node (ref "C68") (pin "2") (pinfunction "2_2") (pintype "passive"))
      (node (ref "D1") (pin "5") (pinfunction "VDD_5") (pintype "power_in"))
      (node (ref "D3") (pin "3") (pinfunction "A_3") (pintype "passive"))
      (node (ref "X1") (pin "VBUS") (pinfunction "VBUS_VBUS") (pintype "bidirectional"))
    )
    (net (code "92") (name "V_IN") (class "Default")
      (node (ref "K1") (pin "1") (pinfunction "1_1") (pintype "passive"))
      (node (ref "LTC4412") (pin "1") (pinfunction "VIN_1") (pintype "bidirectional"))
      (node (ref "SI4465DY_2") (pin "5") (pinfunction "D_5") (pintype "passive"))
      (node (ref "SI4465DY_2") (pin "6") (pinfunction "D_6") (pintype "passive"))
      (node (ref "SI4465DY_2") (pin "7") (pinfunction "D_7") (pintype "passive"))
      (node (ref "SI4465DY_2") (pin "8") (pinfunction "D_8") (pintype "passive"))
    )
    (net (code "93") (name "unconnected-(LDO-NR-Pad4)") (class "Default")
      (node (ref "LDO") (pin "4") (pinfunction "NR_4") (pintype "bidirectional"))
    )
    (net (code "94") (name "unconnected-(LED15-DO-PadDOUT)") (class "Default")
      (node (ref "LED15") (pin "DOUT") (pinfunction "DO_DOUT") (pintype "output"))
    )
    (net (code "95") (name "unconnected-(LED45-DO-PadDOUT)") (class "Default")
      (node (ref "LED45") (pin "DOUT") (pinfunction "DO_DOUT") (pintype "output"))
    )
    (net (code "96") (name "unconnected-(MCU-BOOT0-Pad94)") (class "Default")
      (node (ref "MCU") (pin "94") (pinfunction "BOOT0_94") (pintype "bidirectional"))
    )
    (net (code "97") (name "unconnected-(MCU-PA0-WKUP-Pad22)") (class "Default")
      (node (ref "MCU") (pin "22") (pinfunction "PA0-WKUP_22") (pintype "bidirectional"))
    )
    (net (code "98") (name "unconnected-(MCU-PA2-Pad24)") (class "Default")
      (node (ref "MCU") (pin "24") (pinfunction "PA2_24") (pintype "bidirectional"))
    )
    (net (code "99") (name "unconnected-(MCU-PA3-Pad25)") (class "Default")
      (node (ref "MCU") (pin "25") (pinfunction "PA3_25") (pintype "bidirectional"))
    )
    (net (code "100") (name "unconnected-(MCU-PA4-Pad28)") (class "Default")
      (node (ref "MCU") (pin "28") (pinfunction "PA4_28") (pintype "bidirectional"))
    )
    (net (code "101") (name "unconnected-(MCU-PA5-Pad29)") (class "Default")
      (node (ref "MCU") (pin "29") (pinfunction "PA5_29") (pintype "bidirectional"))
    )
    (net (code "102") (name "unconnected-(MCU-PA6-Pad30)") (class "Default")
      (node (ref "MCU") (pin "30") (pinfunction "PA6_30") (pintype "bidirectional"))
    )
    (net (code "103") (name "unconnected-(MCU-PA7-Pad31)") (class "Default")
      (node (ref "MCU") (pin "31") (pinfunction "PA7_31") (pintype "bidirectional"))
    )
    (net (code "104") (name "unconnected-(MCU-PA8-Pad67)") (class "Default")
      (node (ref "MCU") (pin "67") (pinfunction "PA8_67") (pintype "bidirectional"))
    )
    (net (code "105") (name "unconnected-(MCU-PA9-Pad68)") (class "Default")
      (node (ref "MCU") (pin "68") (pinfunction "PA9_68") (pintype "bidirectional"))
    )
    (net (code "106") (name "unconnected-(MCU-PA10-Pad69)") (class "Default")
      (node (ref "MCU") (pin "69") (pinfunction "PA10_69") (pintype "bidirectional"))
    )
    (net (code "107") (name "unconnected-(MCU-PB0-Pad34)") (class "Default")
      (node (ref "MCU") (pin "34") (pinfunction "PB0_34") (pintype "bidirectional"))
    )
    (net (code "108") (name "unconnected-(MCU-PB1-Pad35)") (class "Default")
      (node (ref "MCU") (pin "35") (pinfunction "PB1_35") (pintype "bidirectional"))
    )
    (net (code "109") (name "unconnected-(MCU-PB2-Pad36)") (class "Default")
      (node (ref "MCU") (pin "36") (pinfunction "PB2_36") (pintype "bidirectional"))
    )
    (net (code "110") (name "unconnected-(MCU-PB5-Pad91)") (class "Default")
      (node (ref "MCU") (pin "91") (pinfunction "PB5_91") (pintype "bidirectional"))
    )
    (net (code "111") (name "unconnected-(MCU-PB6-Pad92)") (class "Default")
      (node (ref "MCU") (pin "92") (pinfunction "PB6_92") (pintype "bidirectional"))
    )
    (net (code "112") (name "unconnected-(MCU-PB7-Pad93)") (class "Default")
      (node (ref "MCU") (pin "93") (pinfunction "PB7_93") (pintype "bidirectional"))
    )
    (net (code "113") (name "unconnected-(MCU-PB8-Pad95)") (class "Default")
      (node (ref "MCU") (pin "95") (pinfunction "PB8_95") (pintype "bidirectional"))
    )
    (net (code "114") (name "unconnected-(MCU-PB9-Pad96)") (class "Default")
      (node (ref "MCU") (pin "96") (pinfunction "PB9_96") (pintype "bidirectional"))
    )
    (net (code "115") (name "unconnected-(MCU-PB10-Pad46)") (class "Default")
      (node (ref "MCU") (pin "46") (pinfunction "PB10_46") (pintype "bidirectional"))
    )
    (net (code "116") (name "unconnected-(MCU-PB11-Pad47)") (class "Default")
      (node (ref "MCU") (pin "47") (pinfunction "PB11_47") (pintype "bidirectional"))
    )
    (net (code "117") (name "unconnected-(MCU-PB12-Pad51)") (class "Default")
      (node (ref "MCU") (pin "51") (pinfunction "PB12_51") (pintype "bidirectional"))
    )
    (net (code "118") (name "unconnected-(MCU-PB13-Pad52)") (class "Default")
      (node (ref "MCU") (pin "52") (pinfunction "PB13_52") (pintype "bidirectional"))
    )
    (net (code "119") (name "unconnected-(MCU-PB14-Pad53)") (class "Default")
      (node (ref "MCU") (pin "53") (pinfunction "PB14_53") (pintype "bidirectional"))
    )
    (net (code "120") (name "unconnected-(MCU-PB15-Pad54)") (class "Default")
      (node (ref "MCU") (pin "54") (pinfunction "PB15_54") (pintype "bidirectional"))
    )
    (net (code "121") (name "unconnected-(MCU-PC0-Pad15)") (class "Default")
      (node (ref "MCU") (pin "15") (pinfunction "PC0_15") (pintype "bidirectional"))
    )
    (net (code "122") (name "unconnected-(MCU-PC1-Pad16)") (class "Default")
      (node (ref "MCU") (pin "16") (pinfunction "PC1_16") (pintype "bidirectional"))
    )
    (net (code "123") (name "unconnected-(MCU-PC2-Pad17)") (class "Default")
      (node (ref "MCU") (pin "17") (pinfunction "PC2_17") (pintype "bidirectional"))
    )
    (net (code "124") (name "unconnected-(MCU-PC3-Pad18)") (class "Default")
      (node (ref "MCU") (pin "18") (pinfunction "PC3_18") (pintype "bidirectional"))
    )
    (net (code "125") (name "unconnected-(MCU-PC4-Pad32)") (class "Default")
      (node (ref "MCU") (pin "32") (pinfunction "PC4_32") (pintype "bidirectional"))
    )
    (net (code "126") (name "unconnected-(MCU-PC5-Pad33)") (class "Default")
      (node (ref "MCU") (pin "33") (pinfunction "PC5_33") (pintype "bidirectional"))
    )
    (net (code "127") (name "unconnected-(MCU-PC6-Pad63)") (class "Default")
      (node (ref "MCU") (pin "63") (pinfunction "PC6_63") (pintype "bidirectional"))
    )
    (net (code "128") (name "unconnected-(MCU-PC7-Pad64)") (class "Default")
      (node (ref "MCU") (pin "64") (pinfunction "PC7_64") (pintype "bidirectional"))
    )
    (net (code "129") (name "unconnected-(MCU-PC8-Pad65)") (class "Default")
      (node (ref "MCU") (pin "65") (pinfunction "PC8_65") (pintype "bidirectional"))
    )
    (net (code "130") (name "unconnected-(MCU-PC9-Pad66)") (class "Default")
      (node (ref "MCU") (pin "66") (pinfunction "PC9_66") (pintype "bidirectional"))
    )
    (net (code "131") (name "unconnected-(MCU-PC10-Pad78)") (class "Default")
      (node (ref "MCU") (pin "78") (pinfunction "PC10_78") (pintype "bidirectional"))
    )
    (net (code "132") (name "unconnected-(MCU-PC11-Pad79)") (class "Default")
      (node (ref "MCU") (pin "79") (pinfunction "PC11_79") (pintype "bidirectional"))
    )
    (net (code "133") (name "unconnected-(MCU-PC12-Pad80)") (class "Default")
      (node (ref "MCU") (pin "80") (pinfunction "PC12_80") (pintype "bidirectional"))
    )
    (net (code "134") (name "unconnected-(MCU-PC13-Pad7)") (class "Default")
      (node (ref "MCU") (pin "7") (pinfunction "PC13_7") (pintype "bidirectional"))
    )
    (net (code "135") (name "unconnected-(MCU-PC14-Pad8)") (class "Default")
      (node (ref "MCU") (pin "8") (pinfunction "PC14_8") (pintype "bidirectional"))
    )
    (net (code "136") (name "unconnected-(MCU-PC15-Pad9)") (class "Default")
      (node (ref "MCU") (pin "9") (pinfunction "PC15_9") (pintype "bidirectional"))
    )
    (net (code "137") (name "unconnected-(MCU-PD0-Pad81)") (class "Default")
      (node (ref "MCU") (pin "81") (pinfunction "PD0_81") (pintype "bidirectional"))
    )
    (net (code "138") (name "unconnected-(MCU-PD1-Pad82)") (class "Default")
      (node (ref "MCU") (pin "82") (pinfunction "PD1_82") (pintype "bidirectional"))
    )
    (net (code "139") (name "unconnected-(MCU-PD2-Pad83)") (class "Default")
      (node (ref "MCU") (pin "83") (pinfunction "PD2_83") (pintype "bidirectional"))
    )
    (net (code "140") (name "unconnected-(MCU-PD3-Pad84)") (class "Default")
      (node (ref "MCU") (pin "84") (pinfunction "PD3_84") (pintype "bidirectional"))
    )
    (net (code "141") (name "unconnected-(MCU-PD4-Pad85)") (class "Default")
      (node (ref "MCU") (pin "85") (pinfunction "PD4_85") (pintype "bidirectional"))
    )
    (net (code "142") (name "unconnected-(MCU-PD5-Pad86)") (class "Default")
      (node (ref "MCU") (pin "86") (pinfunction "PD5_86") (pintype "bidirectional"))
    )
    (net (code "143") (name "unconnected-(MCU-PD6-Pad87)") (class "Default")
      (node (ref "MCU") (pin "87") (pinfunction "PD6_87") (pintype "bidirectional"))
    )
    (net (code "144") (name "unconnected-(MCU-PD7-Pad88)") (class "Default")
      (node (ref "MCU") (pin "88") (pinfunction "PD7_88") (pintype "bidirectional"))
    )
    (net (code "145") (name "unconnected-(MCU-PD8-Pad55)") (class "Default")
      (node (ref "MCU") (pin "55") (pinfunction "PD8_55") (pintype "bidirectional"))
    )
    (net (code "146") (name "unconnected-(MCU-PD9-Pad56)") (class "Default")
      (node (ref "MCU") (pin "56") (pinfunction "PD9_56") (pintype "bidirectional"))
    )
    (net (code "147") (name "unconnected-(MCU-PD10-Pad57)") (class "Default")
      (node (ref "MCU") (pin "57") (pinfunction "PD10_57") (pintype "bidirectional"))
    )
    (net (code "148") (name "unconnected-(MCU-PD11-Pad58)") (class "Default")
      (node (ref "MCU") (pin "58") (pinfunction "PD11_58") (pintype "bidirectional"))
    )
    (net (code "149") (name "unconnected-(MCU-PD12-Pad59)") (class "Default")
      (node (ref "MCU") (pin "59") (pinfunction "PD12_59") (pintype "bidirectional"))
    )
    (net (code "150") (name "unconnected-(MCU-PD13-Pad60)") (class "Default")
      (node (ref "MCU") (pin "60") (pinfunction "PD13_60") (pintype "bidirectional"))
    )
    (net (code "151") (name "unconnected-(MCU-PD14-Pad61)") (class "Default")
      (node (ref "MCU") (pin "61") (pinfunction "PD14_61") (pintype "bidirectional"))
    )
    (net (code "152") (name "unconnected-(MCU-PD15-Pad62)") (class "Default")
      (node (ref "MCU") (pin "62") (pinfunction "PD15_62") (pintype "bidirectional"))
    )
    (net (code "153") (name "unconnected-(MCU-PE0-Pad97)") (class "Default")
      (node (ref "MCU") (pin "97") (pinfunction "PE0_97") (pintype "bidirectional"))
    )
    (net (code "154") (name "unconnected-(MCU-PE1-Pad98)") (class "Default")
      (node (ref "MCU") (pin "98") (pinfunction "PE1_98") (pintype "bidirectional"))
    )
    (net (code "155") (name "unconnected-(MCU-PE2-Pad1)") (class "Default")
      (node (ref "MCU") (pin "1") (pinfunction "PE2_1") (pintype "bidirectional"))
    )
    (net (code "156") (name "unconnected-(MCU-PE3-Pad2)") (class "Default")
      (node (ref "MCU") (pin "2") (pinfunction "PE3_2") (pintype "bidirectional"))
    )
    (net (code "157") (name "unconnected-(MCU-PE4-Pad3)") (class "Default")
      (node (ref "MCU") (pin "3") (pinfunction "PE4_3") (pintype "bidirectional"))
    )
    (net (code "158") (name "unconnected-(MCU-PE5-Pad4)") (class "Default")
      (node (ref "MCU") (pin "4") (pinfunction "PE5_4") (pintype "bidirectional"))
    )
    (net (code "159") (name "unconnected-(MCU-PE6-Pad5)") (class "Default")
      (node (ref "MCU") (pin "5") (pinfunction "PE6_5") (pintype "bidirectional"))
    )
    (net (code "160") (name "unconnected-(MCU-PE7-Pad37)") (class "Default")
      (node (ref "MCU") (pin "37") (pinfunction "PE7_37") (pintype "bidirectional"))
    )
    (net (code "161") (name "unconnected-(MCU-PE8-Pad38)") (class "Default")
      (node (ref "MCU") (pin "38") (pinfunction "PE8_38") (pintype "bidirectional"))
    )
    (net (code "162") (name "unconnected-(MCU-PE10-Pad40)") (class "Default")
      (node (ref "MCU") (pin "40") (pinfunction "PE10_40") (pintype "bidirectional"))
    )
    (net (code "163") (name "unconnected-(MCU-PE12-Pad42)") (class "Default")
      (node (ref "MCU") (pin "42") (pinfunction "PE12_42") (pintype "bidirectional"))
    )
    (net (code "164") (name "unconnected-(MCU-PE13-Pad43)") (class "Default")
      (node (ref "MCU") (pin "43") (pinfunction "PE13_43") (pintype "bidirectional"))
    )
    (net (code "165") (name "unconnected-(MCU-PE14-Pad44)") (class "Default")
      (node (ref "MCU") (pin "44") (pinfunction "PE14_44") (pintype "bidirectional"))
    )
    (net (code "166") (name "unconnected-(MCU-PE15-Pad45)") (class "Default")
      (node (ref "MCU") (pin "45") (pinfunction "PE15_45") (pintype "bidirectional"))
    )
    (net (code "167") (name "unconnected-(MCU-VCAP1-Pad48)") (class "Default")
      (node (ref "MCU") (pin "48") (pinfunction "VCAP1_48") (pintype "bidirectional"))
    )
    (net (code "168") (name "unconnected-(MCU-VCAP2-Pad73)") (class "Default")
      (node (ref "MCU") (pin "73") (pinfunction "VCAP2_73") (pintype "bidirectional"))
    )
    (net (code "169") (name "unconnected-(PUSHPULL-1A-Pad2)") (class "Default")
      (node (ref "PUSHPULL") (pin "2") (pinfunction "1A_2") (pintype "bidirectional"))
    )
    (net (code "170") (name "unconnected-(PUSHPULL-2A-Pad5)") (class "Default")
      (node (ref "PUSHPULL") (pin "5") (pinfunction "2A_5") (pintype "bidirectional"))
    )
  )
)
